# MB_adc_clk.net
KiCad netlist of a schematic drawn in Altium Designer
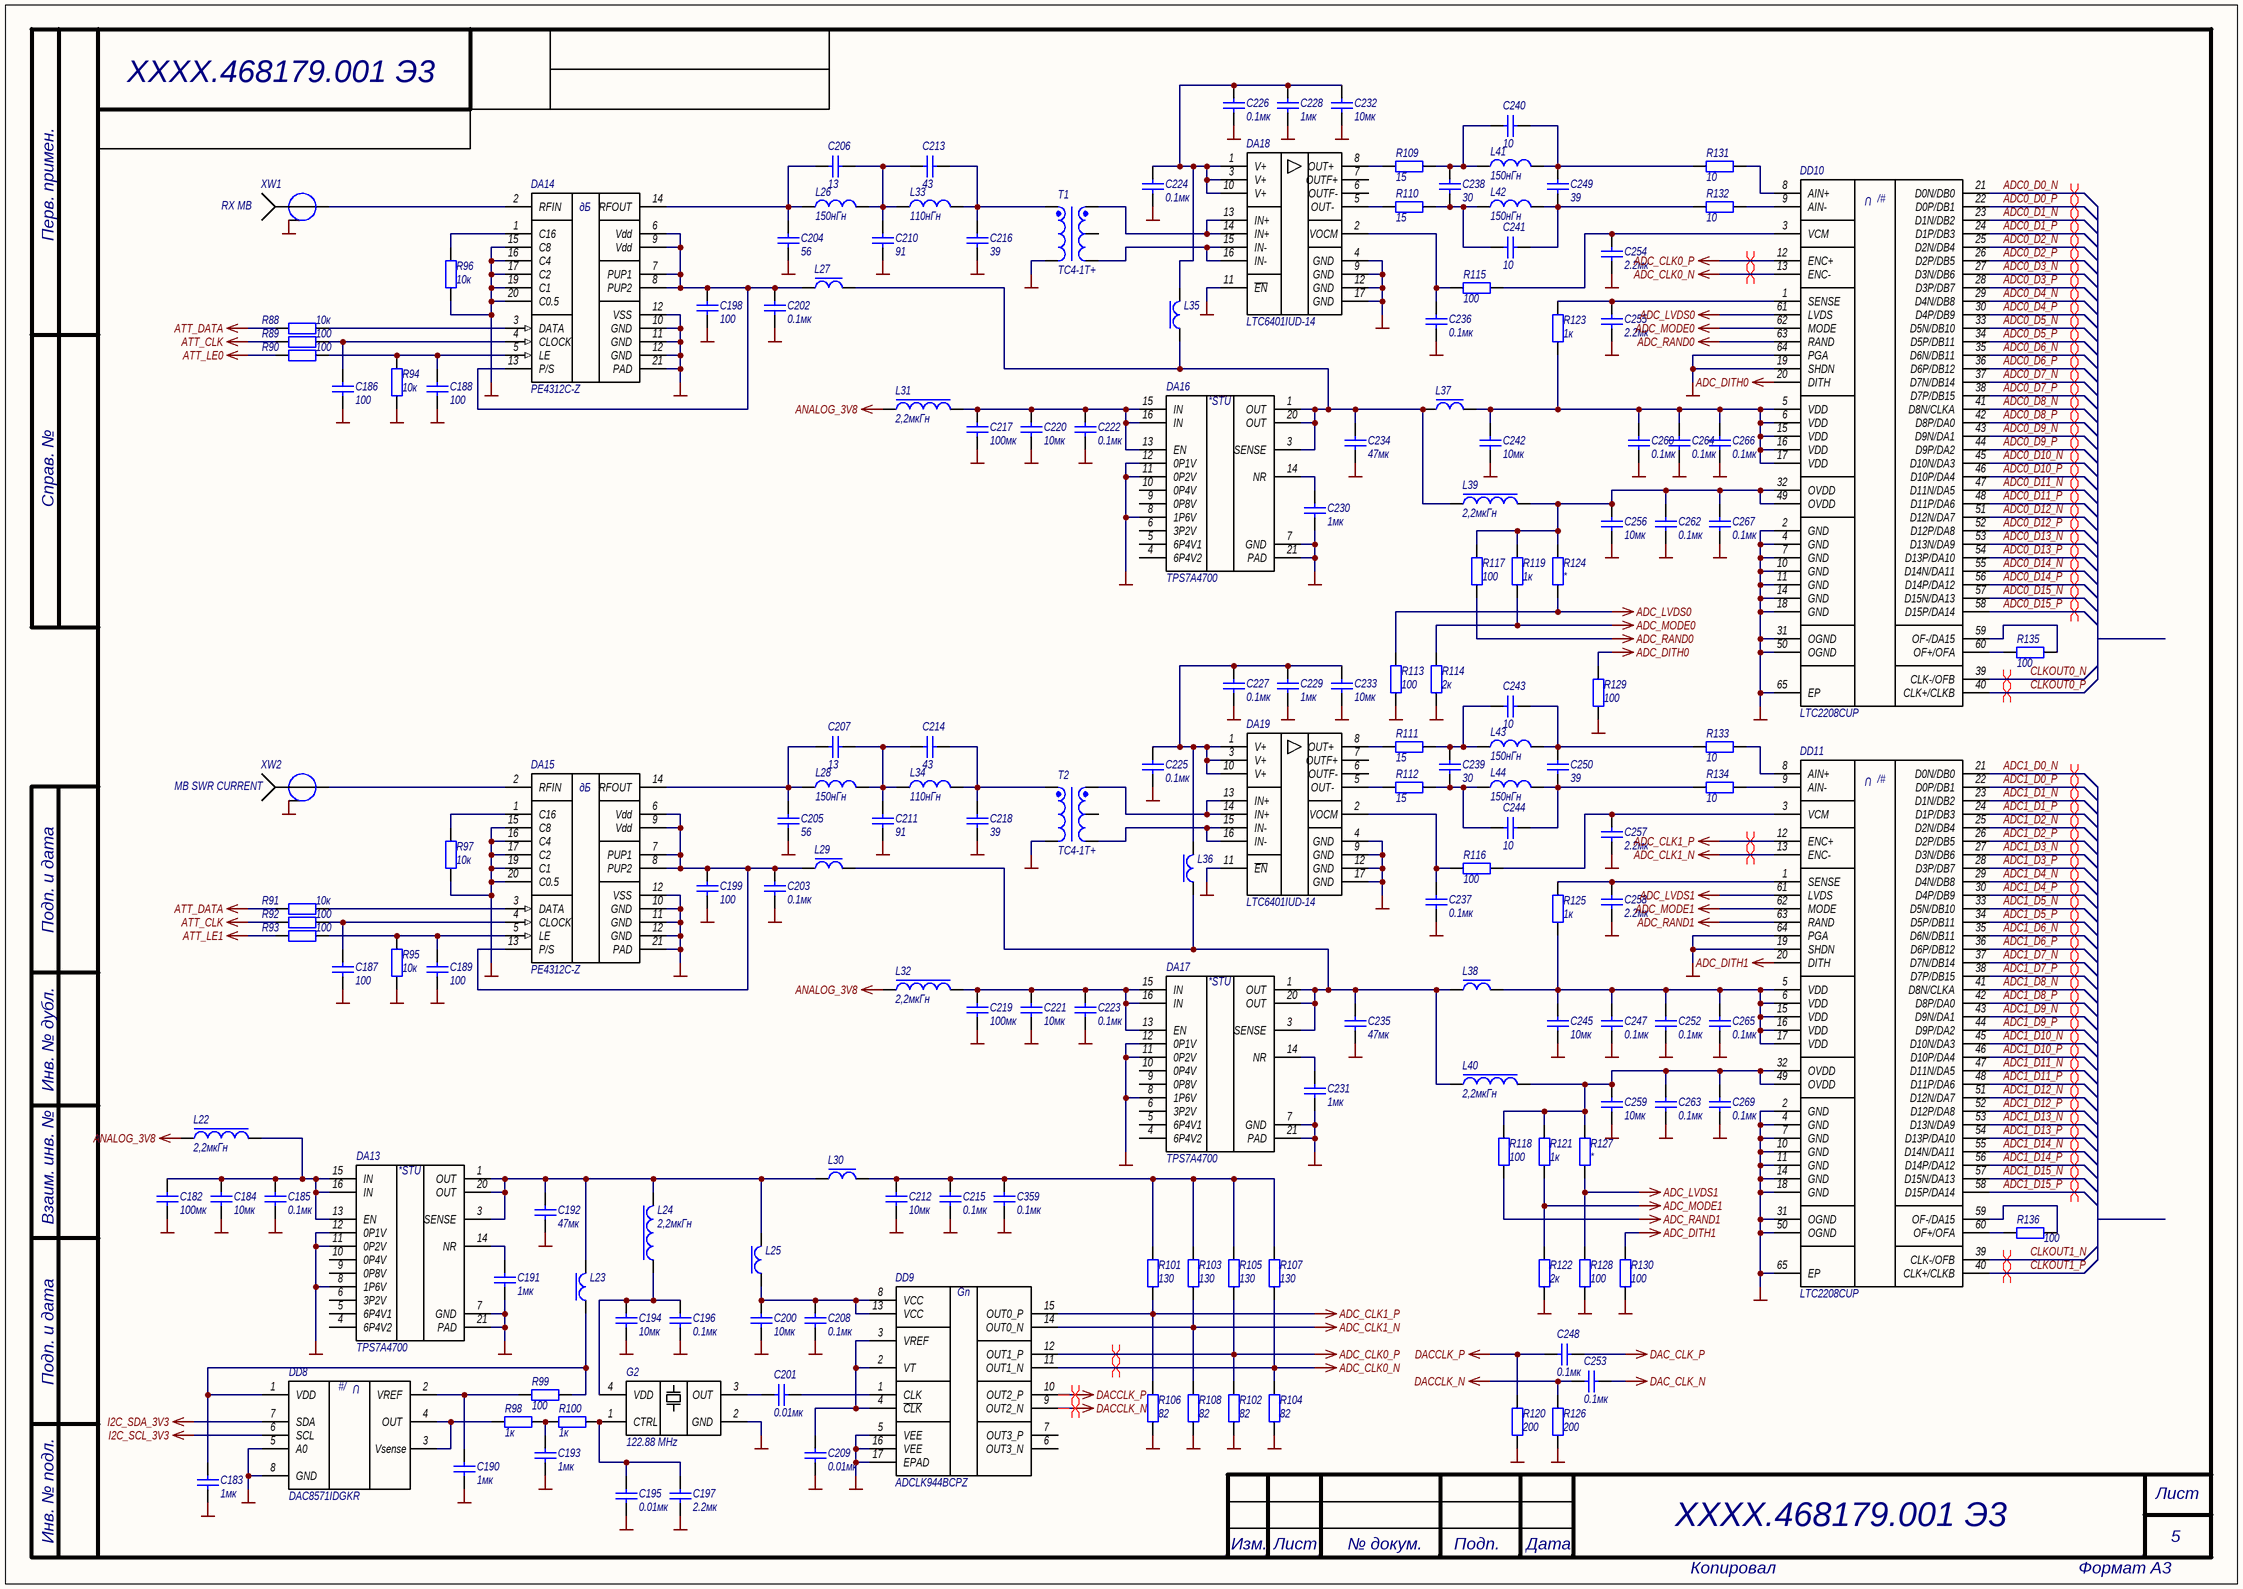
[diagram p0: MB_adc_clk.SchDoc]

(export (version "E")
  (design (tool "Eeschema 10.0.6"))
  (components
    (comp (ref "C182")
      (value "100мк")
      (footprint "CAPC3216X19L")
      (description "Кер. ЧИП-конденсатор")
      (fields (field (name "MANUFACTURER") "Murata") (field (name "TOLERANCE") "±20%"))
      (libsource (lib "nels_caps") (part "Кер.ЧИП конд. 1206 100мкФ X5R 20% 6.3В"))
    )
    (comp (ref "C183")
      (value "1мк")
      (footprint "CAPC1005X06N")
      (description "Кер. ЧИП-конденсатор")
      (fields (field (name "TOLERANCE") "±10%"))
      (libsource (lib "nels_caps") (part "Кер.ЧИП конд. 0402 1мкФ X5R 10%, 10В"))
    )
    (comp (ref "C184")
      (value "10мк")
      (footprint "CAPC1608X08L")
      (description "Кер. ЧИП-конденсатор")
      (fields (field (name "MANUFACTURER") "Murata") (field (name "TOLERANCE") "±20%"))
      (libsource (lib "nels_caps") (part "Кер.ЧИП конд. 0603 10мкФ X5R 20% 6.3В"))
    )
    (comp (ref "C185")
      (value "0.1мк")
      (footprint "CAPC1005X06N")
      (description "Кер. ЧИП-конденсатор")
      (fields (field (name "TOLERANCE") "±10%"))
      (libsource (lib "nels") (part "Кер.ЧИП конд. 0402 0.1мкФ X7R 10%, 16В"))
    )
    (comp (ref "C186")
      (value "100")
      (footprint "CAPC1005X06N")
      (description "Кер. ЧИП-конденсатор")
      (fields (field (name "TOLERANCE") "±5%"))
      (libsource (lib "nels_caps") (part "Кер.ЧИП конд. 0402 100пФ NPO 5%, 50В"))
    )
    (comp (ref "C187")
      (value "100")
      (footprint "CAPC1005X06N")
      (description "Кер. ЧИП-конденсатор")
      (fields (field (name "TOLERANCE") "±5%"))
      (libsource (lib "nels_caps") (part "Кер.ЧИП конд. 0402 100пФ NPO 5%, 50В"))
    )
    (comp (ref "C188")
      (value "100")
      (footprint "CAPC1005X06N")
      (description "Кер. ЧИП-конденсатор")
      (fields (field (name "TOLERANCE") "±5%"))
      (libsource (lib "nels_caps") (part "Кер.ЧИП конд. 0402 100пФ NPO 5%, 50В"))
    )
    (comp (ref "C189")
      (value "100")
      (footprint "CAPC1005X06N")
      (description "Кер. ЧИП-конденсатор")
      (fields (field (name "TOLERANCE") "±5%"))
      (libsource (lib "nels_caps") (part "Кер.ЧИП конд. 0402 100пФ NPO 5%, 50В"))
    )
    (comp (ref "C190")
      (value "1мк")
      (footprint "CAPC1005X06N")
      (description "Кер. ЧИП-конденсатор")
      (fields (field (name "TOLERANCE") "±10%"))
      (libsource (lib "nels_caps") (part "Кер.ЧИП конд. 0402 1мкФ X5R 10%, 10В"))
    )
    (comp (ref "C191")
      (value "1мк")
      (footprint "CAPC1005X06N")
      (description "Кер. ЧИП-конденсатор")
      (fields (field (name "TOLERANCE") "±10%"))
      (libsource (lib "nels_caps") (part "Кер.ЧИП конд. 0402 1мкФ X5R 10%, 10В"))
    )
    (comp (ref "C192")
      (value "47мк")
      (footprint "CAPC2012X12L")
      (description "Кер. ЧИП-конденсатор")
      (fields (field (name "MANUFACTURER") "Murata") (field (name "TOLERANCE") "±20%"))
      (libsource (lib "nels_caps") (part "Кер.ЧИП конд. 0805 47мкФ X5R 20% 10В"))
    )
    (comp (ref "C193")
      (value "1мк")
      (footprint "CAPC1005X06N")
      (description "Кер. ЧИП-конденсатор")
      (fields (field (name "TOLERANCE") "±10%"))
      (libsource (lib "nels_caps") (part "Кер.ЧИП конд. 0402 1мкФ X5R 10%, 10В"))
    )
    (comp (ref "C194")
      (value "10мк")
      (footprint "CAPC1608X08L")
      (description "Кер. ЧИП-конденсатор")
      (fields (field (name "MANUFACTURER") "Murata") (field (name "TOLERANCE") "±20%"))
      (libsource (lib "nels_caps") (part "Кер.ЧИП конд. 0603 10мкФ X5R 20% 6.3В"))
    )
    (comp (ref "C195")
      (value "0.01мк")
      (footprint "CAPC1005X06N")
      (description "Кер. ЧИП-конденсатор")
      (fields (field (name "TOLERANCE") "±20%"))
      (libsource (lib "nels_caps") (part "Кер.ЧИП конд. 0402 0.01мкФ X7R 10%, 50В"))
    )
    (comp (ref "C196")
      (value "0.1мк")
      (footprint "CAPC1005X06N")
      (description "Кер. ЧИП-конденсатор")
      (fields (field (name "TOLERANCE") "±10%"))
      (libsource (lib "nels") (part "Кер.ЧИП конд. 0402 0.1мкФ X7R 10%, 16В"))
    )
    (comp (ref "C197")
      (value "2.2мк")
      (footprint "CAPC1005X06N")
      (description "Кер. ЧИП-конденсатор")
      (fields (field (name "TOLERANCE") "±20%"))
      (libsource (lib "nels_caps") (part "Кер.ЧИП конд. 0402 2.2мкФ X5R 20%, 6.3В"))
    )
    (comp (ref "C198")
      (value "100")
      (footprint "CAPC1005X06N")
      (description "Кер. ЧИП-конденсатор")
      (fields (field (name "TOLERANCE") "±5%"))
      (libsource (lib "nels_caps") (part "Кер.ЧИП конд. 0402 100пФ NPO 5%, 50В"))
    )
    (comp (ref "C199")
      (value "100")
      (footprint "CAPC1005X06N")
      (description "Кер. ЧИП-конденсатор")
      (fields (field (name "TOLERANCE") "±5%"))
      (libsource (lib "nels_caps") (part "Кер.ЧИП конд. 0402 100пФ NPO 5%, 50В"))
    )
    (comp (ref "C200")
      (value "10мк")
      (footprint "CAPC1608X08L")
      (description "Кер. ЧИП-конденсатор")
      (fields (field (name "MANUFACTURER") "Murata") (field (name "TOLERANCE") "±20%"))
      (libsource (lib "nels_caps") (part "Кер.ЧИП конд. 0603 10мкФ X5R 20% 6.3В"))
    )
    (comp (ref "C201")
      (value "0.01мк")
      (footprint "CAPC1005X06N")
      (description "Кер. ЧИП-конденсатор")
      (fields (field (name "TOLERANCE") "±20%"))
      (libsource (lib "nels_caps") (part "Кер.ЧИП конд. 0402 0.01мкФ X7R 10%, 50В"))
    )
    (comp (ref "C202")
      (value "0.1мк")
      (footprint "CAPC1005X06N")
      (description "Кер. ЧИП-конденсатор")
      (fields (field (name "TOLERANCE") "±10%"))
      (libsource (lib "nels") (part "Кер.ЧИП конд. 0402 0.1мкФ X7R 10%, 16В"))
    )
    (comp (ref "C203")
      (value "0.1мк")
      (footprint "CAPC1005X06N")
      (description "Кер. ЧИП-конденсатор")
      (fields (field (name "TOLERANCE") "±10%"))
      (libsource (lib "nels") (part "Кер.ЧИП конд. 0402 0.1мкФ X7R 10%, 16В"))
    )
    (comp (ref "C204")
      (value "56")
      (footprint "CAPC1005X06N")
      (description "Кер. ЧИП-конденсатор")
      (fields (field (name "TOLERANCE") "±5%"))
      (libsource (lib "nels_caps") (part "Кер.ЧИП конд. 0402 56пФ NPO 5%, 50В"))
    )
    (comp (ref "C205")
      (value "56")
      (footprint "CAPC1005X06N")
      (description "Кер. ЧИП-конденсатор")
      (fields (field (name "TOLERANCE") "±5%"))
      (libsource (lib "nels_caps") (part "Кер.ЧИП конд. 0402 56пФ NPO 5%, 50В"))
    )
    (comp (ref "C206")
      (value "13")
      (footprint "CAPC1005X06N")
      (description "Кер. ЧИП-конденсатор")
      (fields (field (name "TOLERANCE") "±5%"))
      (libsource (lib "nels_caps") (part "Кер.ЧИП конд. 0402 13пФ NPO 5%, 50В"))
    )
    (comp (ref "C207")
      (value "13")
      (footprint "CAPC1005X06N")
      (description "Кер. ЧИП-конденсатор")
      (fields (field (name "TOLERANCE") "±5%"))
      (libsource (lib "nels_caps") (part "Кер.ЧИП конд. 0402 13пФ NPO 5%, 50В"))
    )
    (comp (ref "C208")
      (value "0.1мк")
      (footprint "CAPC1005X06N")
      (description "Кер. ЧИП-конденсатор")
      (fields (field (name "TOLERANCE") "±10%"))
      (libsource (lib "nels") (part "Кер.ЧИП конд. 0402 0.1мкФ X7R 10%, 16В"))
    )
    (comp (ref "C209")
      (value "0.01мк")
      (footprint "CAPC1005X06N")
      (description "Кер. ЧИП-конденсатор")
      (fields (field (name "TOLERANCE") "±20%"))
      (libsource (lib "nels_caps") (part "Кер.ЧИП конд. 0402 0.01мкФ X7R 10%, 50В"))
    )
    (comp (ref "C210")
      (value "91")
      (footprint "CAPC1005X06N")
      (description "Кер. ЧИП-конденсатор")
      (fields (field (name "TOLERANCE") "±5%"))
      (libsource (lib "nels_caps") (part "Кер.ЧИП конд. 0402 91пФ NPO 5%, 50В"))
    )
    (comp (ref "C211")
      (value "91")
      (footprint "CAPC1005X06N")
      (description "Кер. ЧИП-конденсатор")
      (fields (field (name "TOLERANCE") "±5%"))
      (libsource (lib "nels_caps") (part "Кер.ЧИП конд. 0402 91пФ NPO 5%, 50В"))
    )
    (comp (ref "C212")
      (value "10мк")
      (footprint "CAPC1608X08L")
      (description "Кер. ЧИП-конденсатор")
      (fields (field (name "MANUFACTURER") "Murata") (field (name "TOLERANCE") "±20%"))
      (libsource (lib "nels_caps") (part "Кер.ЧИП конд. 0603 10мкФ X5R 20% 6.3В"))
    )
    (comp (ref "C213")
      (value "43")
      (footprint "CAPC1005X06N")
      (description "Кер. ЧИП-конденсатор")
      (fields (field (name "TOLERANCE") "±5%"))
      (libsource (lib "nels_caps") (part "Кер.ЧИП конд. 0402 43пФ NPO 5%, 50В"))
    )
    (comp (ref "C214")
      (value "43")
      (footprint "CAPC1005X06N")
      (description "Кер. ЧИП-конденсатор")
      (fields (field (name "TOLERANCE") "±5%"))
      (libsource (lib "nels_caps") (part "Кер.ЧИП конд. 0402 43пФ NPO 5%, 50В"))
    )
    (comp (ref "C215")
      (value "0.1мк")
      (footprint "CAPC1005X06N")
      (description "Кер. ЧИП-конденсатор")
      (fields (field (name "TOLERANCE") "±10%"))
      (libsource (lib "nels") (part "Кер.ЧИП конд. 0402 0.1мкФ X7R 10%, 16В"))
    )
    (comp (ref "C216")
      (value "39")
      (footprint "CAPC1005X06N")
      (description "Кер. ЧИП-конденсатор")
      (fields (field (name "TOLERANCE") "±5%"))
      (libsource (lib "nels_caps") (part "Кер.ЧИП конд. 0402 39пФ NPO 5%, 50В"))
    )
    (comp (ref "C217")
      (value "100мк")
      (footprint "CAPC3216X19L")
      (description "Кер. ЧИП-конденсатор")
      (fields (field (name "MANUFACTURER") "Murata") (field (name "TOLERANCE") "±20%"))
      (libsource (lib "nels_caps") (part "Кер.ЧИП конд. 1206 100мкФ X5R 20% 6.3В"))
    )
    (comp (ref "C218")
      (value "39")
      (footprint "CAPC1005X06N")
      (description "Кер. ЧИП-конденсатор")
      (fields (field (name "TOLERANCE") "±5%"))
      (libsource (lib "nels_caps") (part "Кер.ЧИП конд. 0402 39пФ NPO 5%, 50В"))
    )
    (comp (ref "C219")
      (value "100мк")
      (footprint "CAPC3216X19L")
      (description "Кер. ЧИП-конденсатор")
      (fields (field (name "MANUFACTURER") "Murata") (field (name "TOLERANCE") "±20%"))
      (libsource (lib "nels_caps") (part "Кер.ЧИП конд. 1206 100мкФ X5R 20% 6.3В"))
    )
    (comp (ref "C220")
      (value "10мк")
      (footprint "CAPC1608X08L")
      (description "Кер. ЧИП-конденсатор")
      (fields (field (name "MANUFACTURER") "Murata") (field (name "TOLERANCE") "±20%"))
      (libsource (lib "nels_caps") (part "Кер.ЧИП конд. 0603 10мкФ X5R 20% 6.3В"))
    )
    (comp (ref "C221")
      (value "10мк")
      (footprint "CAPC1608X08L")
      (description "Кер. ЧИП-конденсатор")
      (fields (field (name "MANUFACTURER") "Murata") (field (name "TOLERANCE") "±20%"))
      (libsource (lib "nels_caps") (part "Кер.ЧИП конд. 0603 10мкФ X5R 20% 6.3В"))
    )
    (comp (ref "C222")
      (value "0.1мк")
      (footprint "CAPC1005X06N")
      (description "Кер. ЧИП-конденсатор")
      (fields (field (name "TOLERANCE") "±10%"))
      (libsource (lib "nels") (part "Кер.ЧИП конд. 0402 0.1мкФ X7R 10%, 16В"))
    )
    (comp (ref "C223")
      (value "0.1мк")
      (footprint "CAPC1005X06N")
      (description "Кер. ЧИП-конденсатор")
      (fields (field (name "TOLERANCE") "±10%"))
      (libsource (lib "nels") (part "Кер.ЧИП конд. 0402 0.1мкФ X7R 10%, 16В"))
    )
    (comp (ref "C224")
      (value "0.1мк")
      (footprint "CAPC1005X06N")
      (description "Кер. ЧИП-конденсатор")
      (fields (field (name "TOLERANCE") "±10%"))
      (libsource (lib "nels") (part "Кер.ЧИП конд. 0402 0.1мкФ X7R 10%, 16В"))
    )
    (comp (ref "C225")
      (value "0.1мк")
      (footprint "CAPC1005X06N")
      (description "Кер. ЧИП-конденсатор")
      (fields (field (name "TOLERANCE") "±10%"))
      (libsource (lib "nels") (part "Кер.ЧИП конд. 0402 0.1мкФ X7R 10%, 16В"))
    )
    (comp (ref "C226")
      (value "0.1мк")
      (footprint "CAPC1005X06N")
      (description "Кер. ЧИП-конденсатор")
      (fields (field (name "TOLERANCE") "±10%"))
      (libsource (lib "nels") (part "Кер.ЧИП конд. 0402 0.1мкФ X7R 10%, 16В"))
    )
    (comp (ref "C227")
      (value "0.1мк")
      (footprint "CAPC1005X06N")
      (description "Кер. ЧИП-конденсатор")
      (fields (field (name "TOLERANCE") "±10%"))
      (libsource (lib "nels") (part "Кер.ЧИП конд. 0402 0.1мкФ X7R 10%, 16В"))
    )
    (comp (ref "C228")
      (value "1мк")
      (footprint "CAPC1005X06N")
      (description "Кер. ЧИП-конденсатор")
      (fields (field (name "TOLERANCE") "±10%"))
      (libsource (lib "nels") (part "Кер.ЧИП конд. 0402 1мкФ X5R 10%, 10В"))
    )
    (comp (ref "C229")
      (value "1мк")
      (footprint "CAPC1005X06N")
      (description "Кер. ЧИП-конденсатор")
      (fields (field (name "TOLERANCE") "±10%"))
      (libsource (lib "nels") (part "Кер.ЧИП конд. 0402 1мкФ X5R 10%, 10В"))
    )
    (comp (ref "C230")
      (value "1мк")
      (footprint "CAPC1005X06N")
      (description "Кер. ЧИП-конденсатор")
      (fields (field (name "TOLERANCE") "±10%"))
      (libsource (lib "nels_caps") (part "Кер.ЧИП конд. 0402 1мкФ X5R 10%, 10В"))
    )
    (comp (ref "C231")
      (value "1мк")
      (footprint "CAPC1005X06N")
      (description "Кер. ЧИП-конденсатор")
      (fields (field (name "TOLERANCE") "±10%"))
      (libsource (lib "nels_caps") (part "Кер.ЧИП конд. 0402 1мкФ X5R 10%, 10В"))
    )
    (comp (ref "C232")
      (value "10мк")
      (footprint "CAPC1608X08L")
      (description "Кер. ЧИП-конденсатор")
      (fields (field (name "MANUFACTURER") "Murata") (field (name "TOLERANCE") "±20%"))
      (libsource (lib "nels_caps") (part "Кер.ЧИП конд. 0603 10мкФ X5R 20% 6.3В"))
    )
    (comp (ref "C233")
      (value "10мк")
      (footprint "CAPC1608X08L")
      (description "Кер. ЧИП-конденсатор")
      (fields (field (name "MANUFACTURER") "Murata") (field (name "TOLERANCE") "±20%"))
      (libsource (lib "nels_caps") (part "Кер.ЧИП конд. 0603 10мкФ X5R 20% 6.3В"))
    )
    (comp (ref "C234")
      (value "47мк")
      (footprint "CAPC2012X12L")
      (description "Кер. ЧИП-конденсатор")
      (fields (field (name "MANUFACTURER") "Murata") (field (name "TOLERANCE") "±20%"))
      (libsource (lib "nels_caps") (part "Кер.ЧИП конд. 0805 47мкФ X5R 20% 10В"))
    )
    (comp (ref "C235")
      (value "47мк")
      (footprint "CAPC2012X12L")
      (description "Кер. ЧИП-конденсатор")
      (fields (field (name "MANUFACTURER") "Murata") (field (name "TOLERANCE") "±20%"))
      (libsource (lib "nels_caps") (part "Кер.ЧИП конд. 0805 47мкФ X5R 20% 10В"))
    )
    (comp (ref "C236")
      (value "0.1мк")
      (footprint "CAPC1005X06N")
      (description "Кер. ЧИП-конденсатор")
      (fields (field (name "TOLERANCE") "±10%"))
      (libsource (lib "nels") (part "Кер.ЧИП конд. 0402 0.1мкФ X7R 10%, 16В"))
    )
    (comp (ref "C237")
      (value "0.1мк")
      (footprint "CAPC1005X06N")
      (description "Кер. ЧИП-конденсатор")
      (fields (field (name "TOLERANCE") "±10%"))
      (libsource (lib "nels") (part "Кер.ЧИП конд. 0402 0.1мкФ X7R 10%, 16В"))
    )
    (comp (ref "C238")
      (value "30")
      (footprint "CAPC1005X06N")
      (description "Кер. ЧИП-конденсатор")
      (fields (field (name "TOLERANCE") "±5%"))
      (libsource (lib "nels_caps") (part "Кер.ЧИП конд. 0402 30пФ NPO 5%, 50В"))
    )
    (comp (ref "C239")
      (value "30")
      (footprint "CAPC1005X06N")
      (description "Кер. ЧИП-конденсатор")
      (fields (field (name "TOLERANCE") "±5%"))
      (libsource (lib "nels_caps") (part "Кер.ЧИП конд. 0402 30пФ NPO 5%, 50В"))
    )
    (comp (ref "C240")
      (value "10")
      (footprint "CAPC1005X06N")
      (description "Кер. ЧИП-конденсатор")
      (fields (field (name "TOLERANCE") "±5%"))
      (libsource (lib "nels_caps") (part "Кер.ЧИП конд. 0402 10пФ NPO 5%, 50В"))
    )
    (comp (ref "C241")
      (value "10")
      (footprint "CAPC1005X06N")
      (description "Кер. ЧИП-конденсатор")
      (fields (field (name "TOLERANCE") "±5%"))
      (libsource (lib "nels_caps") (part "Кер.ЧИП конд. 0402 10пФ NPO 5%, 50В"))
    )
    (comp (ref "C242")
      (value "10мк")
      (footprint "CAPC1608X08L")
      (description "Кер. ЧИП-конденсатор")
      (fields (field (name "MANUFACTURER") "Murata") (field (name "TOLERANCE") "±20%"))
      (libsource (lib "nels_caps") (part "Кер.ЧИП конд. 0603 10мкФ X5R 20% 6.3В"))
    )
    (comp (ref "C243")
      (value "10")
      (footprint "CAPC1005X06N")
      (description "Кер. ЧИП-конденсатор")
      (fields (field (name "TOLERANCE") "±5%"))
      (libsource (lib "nels_caps") (part "Кер.ЧИП конд. 0402 10пФ NPO 5%, 50В"))
    )
    (comp (ref "C244")
      (value "10")
      (footprint "CAPC1005X06N")
      (description "Кер. ЧИП-конденсатор")
      (fields (field (name "TOLERANCE") "±5%"))
      (libsource (lib "nels_caps") (part "Кер.ЧИП конд. 0402 10пФ NPO 5%, 50В"))
    )
    (comp (ref "C245")
      (value "10мк")
      (footprint "CAPC1608X08L")
      (description "Кер. ЧИП-конденсатор")
      (fields (field (name "MANUFACTURER") "Murata") (field (name "TOLERANCE") "±20%"))
      (libsource (lib "nels_caps") (part "Кер.ЧИП конд. 0603 10мкФ X5R 20% 6.3В"))
    )
    (comp (ref "C247")
      (value "0.1мк")
      (footprint "CAPC1005X06N")
      (description "Кер. ЧИП-конденсатор")
      (fields (field (name "TOLERANCE") "±10%"))
      (libsource (lib "nels") (part "Кер.ЧИП конд. 0402 0.1мкФ X7R 10%, 16В"))
    )
    (comp (ref "C248")
      (value "0.1мк")
      (footprint "CAPC1005X06N")
      (description "Кер. ЧИП-конденсатор")
      (fields (field (name "TOLERANCE") "±10%"))
      (libsource (lib "nels") (part "Кер.ЧИП конд. 0402 0.1мкФ X7R 10%, 16В"))
    )
    (comp (ref "C249")
      (value "39")
      (footprint "CAPC1005X06N")
      (description "Кер. ЧИП-конденсатор")
      (fields (field (name "TOLERANCE") "±5%"))
      (libsource (lib "nels_caps") (part "Кер.ЧИП конд. 0402 39пФ NPO 5%, 50В"))
    )
    (comp (ref "C250")
      (value "39")
      (footprint "CAPC1005X06N")
      (description "Кер. ЧИП-конденсатор")
      (fields (field (name "TOLERANCE") "±5%"))
      (libsource (lib "nels_caps") (part "Кер.ЧИП конд. 0402 39пФ NPO 5%, 50В"))
    )
    (comp (ref "C252")
      (value "0.1мк")
      (footprint "CAPC1005X06N")
      (description "Кер. ЧИП-конденсатор")
      (fields (field (name "TOLERANCE") "±10%"))
      (libsource (lib "nels") (part "Кер.ЧИП конд. 0402 0.1мкФ X7R 10%, 16В"))
    )
    (comp (ref "C253")
      (value "0.1мк")
      (footprint "CAPC1005X06N")
      (description "Кер. ЧИП-конденсатор")
      (fields (field (name "TOLERANCE") "±10%"))
      (libsource (lib "nels") (part "Кер.ЧИП конд. 0402 0.1мкФ X7R 10%, 16В"))
    )
    (comp (ref "C254")
      (value "2.2мк")
      (footprint "CAPC1005X06N")
      (description "Кер. ЧИП-конденсатор")
      (fields (field (name "TOLERANCE") "±20%"))
      (libsource (lib "nels_caps") (part "Кер.ЧИП конд. 0402 2.2мкФ X5R 20%, 6.3В"))
    )
    (comp (ref "C255")
      (value "2.2мк")
      (footprint "CAPC1005X06N")
      (description "Кер. ЧИП-конденсатор")
      (fields (field (name "TOLERANCE") "±20%"))
      (libsource (lib "nels_caps") (part "Кер.ЧИП конд. 0402 2.2мкФ X5R 20%, 6.3В"))
    )
    (comp (ref "C256")
      (value "10мк")
      (footprint "CAPC1608X08L")
      (description "Кер. ЧИП-конденсатор")
      (fields (field (name "MANUFACTURER") "Murata") (field (name "TOLERANCE") "±20%"))
      (libsource (lib "nels_caps") (part "Кер.ЧИП конд. 0603 10мкФ X5R 20% 6.3В"))
    )
    (comp (ref "C257")
      (value "2.2мк")
      (footprint "CAPC1005X06N")
      (description "Кер. ЧИП-конденсатор")
      (fields (field (name "TOLERANCE") "±20%"))
      (libsource (lib "nels_caps") (part "Кер.ЧИП конд. 0402 2.2мкФ X5R 20%, 6.3В"))
    )
    (comp (ref "C258")
      (value "2.2мк")
      (footprint "CAPC1005X06N")
      (description "Кер. ЧИП-конденсатор")
      (fields (field (name "TOLERANCE") "±20%"))
      (libsource (lib "nels_caps") (part "Кер.ЧИП конд. 0402 2.2мкФ X5R 20%, 6.3В"))
    )
    (comp (ref "C259")
      (value "10мк")
      (footprint "CAPC1608X08L")
      (description "Кер. ЧИП-конденсатор")
      (fields (field (name "MANUFACTURER") "Murata") (field (name "TOLERANCE") "±20%"))
      (libsource (lib "nels_caps") (part "Кер.ЧИП конд. 0603 10мкФ X5R 20% 6.3В"))
    )
    (comp (ref "C260")
      (value "0.1мк")
      (footprint "CAPC1005X06N")
      (description "Кер. ЧИП-конденсатор")
      (fields (field (name "TOLERANCE") "±10%"))
      (libsource (lib "nels") (part "Кер.ЧИП конд. 0402 0.1мкФ X7R 10%, 16В"))
    )
    (comp (ref "C262")
      (value "0.1мк")
      (footprint "CAPC1005X06N")
      (description "Кер. ЧИП-конденсатор")
      (fields (field (name "TOLERANCE") "±10%"))
      (libsource (lib "nels") (part "Кер.ЧИП конд. 0402 0.1мкФ X7R 10%, 16В"))
    )
    (comp (ref "C263")
      (value "0.1мк")
      (footprint "CAPC1005X06N")
      (description "Кер. ЧИП-конденсатор")
      (fields (field (name "TOLERANCE") "±10%"))
      (libsource (lib "nels") (part "Кер.ЧИП конд. 0402 0.1мкФ X7R 10%, 16В"))
    )
    (comp (ref "C264")
      (value "0.1мк")
      (footprint "CAPC1005X06N")
      (description "Кер. ЧИП-конденсатор")
      (fields (field (name "TOLERANCE") "±10%"))
      (libsource (lib "nels") (part "Кер.ЧИП конд. 0402 0.1мкФ X7R 10%, 16В"))
    )
    (comp (ref "C265")
      (value "0.1мк")
      (footprint "CAPC1005X06N")
      (description "Кер. ЧИП-конденсатор")
      (fields (field (name "TOLERANCE") "±10%"))
      (libsource (lib "nels") (part "Кер.ЧИП конд. 0402 0.1мкФ X7R 10%, 16В"))
    )
    (comp (ref "C266")
      (value "0.1мк")
      (footprint "CAPC1005X06N")
      (description "Кер. ЧИП-конденсатор")
      (fields (field (name "TOLERANCE") "±10%"))
      (libsource (lib "nels") (part "Кер.ЧИП конд. 0402 0.1мкФ X7R 10%, 16В"))
    )
    (comp (ref "C267")
      (value "0.1мк")
      (footprint "CAPC1005X06N")
      (description "Кер. ЧИП-конденсатор")
      (fields (field (name "TOLERANCE") "±10%"))
      (libsource (lib "nels") (part "Кер.ЧИП конд. 0402 0.1мкФ X7R 10%, 16В"))
    )
    (comp (ref "C269")
      (value "0.1мк")
      (footprint "CAPC1005X06N")
      (description "Кер. ЧИП-конденсатор")
      (fields (field (name "TOLERANCE") "±10%"))
      (libsource (lib "nels") (part "Кер.ЧИП конд. 0402 0.1мкФ X7R 10%, 16В"))
    )
    (comp (ref "C359")
      (value "0.1мк")
      (footprint "CAPC1005X06N")
      (description "Кер. ЧИП-конденсатор")
      (fields (field (name "TOLERANCE") "±10%"))
      (libsource (lib "nels") (part "Кер.ЧИП конд. 0402 0.1мкФ X7R 10%, 16В"))
    )
    (comp (ref "DA13")
      (value "TPS7A4700")
      (footprint "QFN65P500X500X100_HS-21L")
      (description "36-V, 1-A, 4-µVRMS, RF LDO Voltage Regulator")
      (fields (field (name "MANUFACTURER") "TI"))
      (libsource (lib "nels_chip") (part "Микросхема TPS7A4700RGW"))
    )
    (comp (ref "DA14")
      (value "PE4312C-Z")
      (footprint "QFN50P400X400X80_HS-21L")
      (description "RF Digital Step Attenuator 6-bit, 31.5 dB, 1 MHz–4 GHz")
      (fields (field (name "MANUFACTURER") "Peregrine"))
      (libsource (lib "nels_chip") (part "Микросхема PE4312C-Z"))
    )
    (comp (ref "DA15")
      (value "PE4312C-Z")
      (footprint "QFN50P400X400X80_HS-21L")
      (description "RF Digital Step Attenuator 6-bit, 31.5 dB, 1 MHz–4 GHz")
      (fields (field (name "MANUFACTURER") "Peregrine"))
      (libsource (lib "nels_chip") (part "Микросхема PE4312C-Z"))
    )
    (comp (ref "DA16")
      (value "TPS7A4700")
      (footprint "QFN65P500X500X100_HS-21L")
      (description "36-V, 1-A, 4-µVRMS, RF LDO Voltage Regulator")
      (fields (field (name "MANUFACTURER") "TI"))
      (libsource (lib "nels_chip") (part "Микросхема TPS7A4700RGW"))
    )
    (comp (ref "DA17")
      (value "TPS7A4700")
      (footprint "QFN65P500X500X100_HS-21L")
      (description "36-V, 1-A, 4-µVRMS, RF LDO Voltage Regulator")
      (fields (field (name "MANUFACTURER") "TI"))
      (libsource (lib "nels_chip") (part "Микросхема TPS7A4700RGW"))
    )
    (comp (ref "DA18")
      (value "LTC6401IUD-14")
      (footprint "QFN50P300X300X75_HS-17L")
      (description "2GHz Low Noise, Low  Distortion Differential ADC  Driver for DC-140MHz")
      (fields (field (name "MANUFACTURER") "LINEAR TECHNOLOGY"))
      (libsource (lib "nels_chip") (part "Микросхема LTC6401IUD-14"))
    )
    (comp (ref "DA19")
      (value "LTC6401IUD-14")
      (footprint "QFN50P300X300X75_HS-17L")
      (description "2GHz Low Noise, Low  Distortion Differential ADC  Driver for DC-140MHz")
      (fields (field (name "MANUFACTURER") "LINEAR TECHNOLOGY"))
      (libsource (lib "nels_chip") (part "Микросхема LTC6401IUD-14"))
    )
    (comp (ref "DD8")
      (value "DAC8571IDGKR")
      (footprint "TSOP65P490X110-8L")
      (description "16-BIT, LOW POWER, VOLTAGE OUTPUT, I2C INTERFACE DIGITAL-TO-ANALOG  CONVERTER")
      (fields (field (name "MANUFACTURER") "TI"))
      (libsource (lib "nels_chip") (part "Микросхема DAC8571IDGKR"))
    )
    (comp (ref "DD9")
      (value "ADCLK944BCPZ")
      (footprint "QFN50P300X300X100_HS-17L")
      (description "2.5 V/3.3 V, Four LVPECL Outputs,  SiGe Clock Fanout Buffer")
      (fields (field (name "MANUFACTURER") "TI"))
      (libsource (lib "nels_chip") (part "Микросхема ADCLK944BCPZ"))
    )
    (comp (ref "DD10")
      (value "LTC2208CUP")
      (footprint "QFN50P900X900X100_HS-65L")
      (description "16-Bit, 130Msps ADC")
      (libsource (lib "nels_chip") (part "Микросхема LTC2208CUP"))
    )
    (comp (ref "DD11")
      (value "LTC2208CUP")
      (footprint "QFN50P900X900X100_HS-65L")
      (description "16-Bit, 130Msps ADC")
      (libsource (lib "nels_chip") (part "Микросхема LTC2208CUP"))
    )
    (comp (ref "G2")
      (value "122.88 MHz")
      (footprint "CVHD-950 Model")
      (description "122.88 MHz Ultra-Low Phase Noise Oscillator")
      (fields (field (name "MANUFACTURER") "Crystek crystals"))
      (libsource (lib "nels_other") (part "Генератор кварцевый CVHD-950-122.880"))
    )
    (comp (ref "L22")
      (value "2,2мкГн")
      (footprint "CSAB0420")
      (description "Molding Power Choke")
      (fields
        (field (name "MANUFACTURER") "Vishay")
        (field (name "MANUFACTURERPARTNUMBER") "IHLP1616ABER1R0M11")
      )
      (libsource (lib "nels_ind") (part "ЧИП индуктивность CSAB0420-2R2M"))
    )
    (comp (ref "L23")
      (value "BLM18PG121SN1D")
      (footprint "INDC1608X08L")
      (description "SMD EMI Suppression Filter EMIFIL")
      (fields (field (name "MANUFACTURER") "Murata"))
      (libsource (lib "nels_ind") (part "ЧИП дроссель 0603 BLM18PG121SN1D"))
    )
    (comp (ref "L24")
      (value "2,2мкГн")
      (footprint "CSAB0420")
      (description "Molding Power Choke")
      (fields
        (field (name "MANUFACTURER") "Vishay")
        (field (name "MANUFACTURERPARTNUMBER") "IHLP1616ABER1R0M11")
      )
      (libsource (lib "nels_ind") (part "ЧИП индуктивность CSAB0420-2R2M"))
    )
    (comp (ref "L25")
      (value "BLM18PG121SN1D")
      (footprint "INDC1608X08L")
      (description "SMD EMI Suppression Filter EMIFIL")
      (fields (field (name "MANUFACTURER") "Murata"))
      (libsource (lib "nels_ind") (part "ЧИП дроссель 0603 BLM18PG121SN1D"))
    )
    (comp (ref "L26")
      (value "150нГн")
      (footprint "INDC0805CS")
      (libsource (lib "nels_ind") (part "ЧИП индуктивность 0805CS-151XGL"))
    )
    (comp (ref "L27")
      (value "BLM18PG121SN1D")
      (footprint "INDC1608X08L")
      (description "SMD EMI Suppression Filter EMIFIL")
      (fields (field (name "MANUFACTURER") "Murata"))
      (libsource (lib "nels_ind") (part "ЧИП дроссель 0603 BLM18PG121SN1D"))
    )
    (comp (ref "L28")
      (value "150нГн")
      (footprint "INDC0805CS")
      (libsource (lib "nels_ind") (part "ЧИП индуктивность 0805CS-151XGL"))
    )
    (comp (ref "L29")
      (value "BLM18PG121SN1D")
      (footprint "INDC1608X08L")
      (description "SMD EMI Suppression Filter EMIFIL")
      (fields (field (name "MANUFACTURER") "Murata"))
      (libsource (lib "nels_ind") (part "ЧИП дроссель 0603 BLM18PG121SN1D"))
    )
    (comp (ref "L30")
      (value "BLM18PG121SN1D")
      (footprint "INDC1608X08L")
      (description "SMD EMI Suppression Filter EMIFIL")
      (fields (field (name "MANUFACTURER") "Murata"))
      (libsource (lib "nels_ind") (part "ЧИП дроссель 0603 BLM18PG121SN1D"))
    )
    (comp (ref "L31")
      (value "2,2мкГн")
      (footprint "CSAB0420")
      (description "Molding Power Choke")
      (fields
        (field (name "MANUFACTURER") "Vishay")
        (field (name "MANUFACTURERPARTNUMBER") "IHLP1616ABER1R0M11")
      )
      (libsource (lib "nels_ind") (part "ЧИП индуктивность CSAB0420-2R2M"))
    )
    (comp (ref "L32")
      (value "2,2мкГн")
      (footprint "CSAB0420")
      (description "Molding Power Choke")
      (fields
        (field (name "MANUFACTURER") "Vishay")
        (field (name "MANUFACTURERPARTNUMBER") "IHLP1616ABER1R0M11")
      )
      (libsource (lib "nels_ind") (part "ЧИП индуктивность CSAB0420-2R2M"))
    )
    (comp (ref "L33")
      (value "110нГн")
      (footprint "INDC0805CS")
      (libsource (lib "nels_ind") (part "ЧИП индуктивность 0805CS-111XGL"))
    )
    (comp (ref "L34")
      (value "110нГн")
      (footprint "INDC0805CS")
      (libsource (lib "nels_ind") (part "ЧИП индуктивность 0805CS-111XGL"))
    )
    (comp (ref "L35")
      (value "BLM18PG121SN1D")
      (footprint "INDC1608X08L")
      (description "SMD EMI Suppression Filter EMIFIL")
      (fields (field (name "MANUFACTURER") "Murata"))
      (libsource (lib "nels_ind") (part "ЧИП дроссель 0603 BLM18PG121SN1D"))
    )
    (comp (ref "L36")
      (value "BLM18PG121SN1D")
      (footprint "INDC1608X08L")
      (description "SMD EMI Suppression Filter EMIFIL")
      (fields (field (name "MANUFACTURER") "Murata"))
      (libsource (lib "nels_ind") (part "ЧИП дроссель 0603 BLM18PG121SN1D"))
    )
    (comp (ref "L37")
      (value "BLM18PG121SN1D")
      (footprint "INDC1608X08L")
      (description "SMD EMI Suppression Filter EMIFIL")
      (fields (field (name "MANUFACTURER") "Murata"))
      (libsource (lib "nels_ind") (part "ЧИП дроссель 0603 BLM18PG121SN1D"))
    )
    (comp (ref "L38")
      (value "BLM18PG121SN1D")
      (footprint "INDC1608X08L")
      (description "SMD EMI Suppression Filter EMIFIL")
      (fields (field (name "MANUFACTURER") "Murata"))
      (libsource (lib "nels_ind") (part "ЧИП дроссель 0603 BLM18PG121SN1D"))
    )
    (comp (ref "L39")
      (value "2,2мкГн")
      (footprint "CSAB0420")
      (description "Molding Power Choke")
      (fields
        (field (name "MANUFACTURER") "Vishay")
        (field (name "MANUFACTURERPARTNUMBER") "IHLP1616ABER1R0M11")
      )
      (libsource (lib "nels_ind") (part "ЧИП индуктивность CSAB0420-2R2M"))
    )
    (comp (ref "L40")
      (value "2,2мкГн")
      (footprint "CSAB0420")
      (description "Molding Power Choke")
      (fields
        (field (name "MANUFACTURER") "Vishay")
        (field (name "MANUFACTURERPARTNUMBER") "IHLP1616ABER1R0M11")
      )
      (libsource (lib "nels_ind") (part "ЧИП индуктивность CSAB0420-2R2M"))
    )
    (comp (ref "L41")
      (value "150нГн")
      (footprint "INDC0805CS")
      (libsource (lib "nels_ind") (part "ЧИП индуктивность 0805CS-150XJL"))
    )
    (comp (ref "L42")
      (value "150нГн")
      (footprint "INDC0805CS")
      (libsource (lib "nels_ind") (part "ЧИП индуктивность 0805CS-150XJL"))
    )
    (comp (ref "L43")
      (value "150нГн")
      (footprint "INDC0805CS")
      (libsource (lib "nels_ind") (part "ЧИП индуктивность 0805CS-150XJL"))
    )
    (comp (ref "L44")
      (value "150нГн")
      (footprint "INDC0805CS")
      (libsource (lib "nels_ind") (part "ЧИП индуктивность 0805CS-150XJL"))
    )
    (comp (ref "R88")
      (value "10к")
      (footprint "RESC1005X06N")
      (description "ЧИП-резистор")
      (fields (field (name "TOLERANCE") "±5%"))
      (libsource (lib "") (part "Чип резистор 0402 10 кОм, 5%_1"))
    )
    (comp (ref "R89")
      (value "100")
      (footprint "RESC1005X06N")
      (description "ЧИП-резистор")
      (fields (field (name "TOLERANCE") "±5%"))
      (libsource (lib "") (part "Чип резистор 0402 100 Ом, 5%_1"))
    )
    (comp (ref "R90")
      (value "100")
      (footprint "RESC1005X06N")
      (description "ЧИП-резистор")
      (fields (field (name "TOLERANCE") "±5%"))
      (libsource (lib "") (part "Чип резистор 0402 100 Ом, 5%_1"))
    )
    (comp (ref "R91")
      (value "10к")
      (footprint "RESC1005X06N")
      (description "ЧИП-резистор")
      (fields (field (name "TOLERANCE") "±5%"))
      (libsource (lib "") (part "Чип резистор 0402 10 кОм, 5%_1"))
    )
    (comp (ref "R92")
      (value "100")
      (footprint "RESC1005X06N")
      (description "ЧИП-резистор")
      (fields (field (name "TOLERANCE") "±5%"))
      (libsource (lib "") (part "Чип резистор 0402 100 Ом, 5%_1"))
    )
    (comp (ref "R93")
      (value "100")
      (footprint "RESC1005X06N")
      (description "ЧИП-резистор")
      (fields (field (name "TOLERANCE") "±5%"))
      (libsource (lib "") (part "Чип резистор 0402 100 Ом, 5%_1"))
    )
    (comp (ref "R94")
      (value "10к")
      (footprint "RESC1005X06N")
      (description "ЧИП-резистор")
      (fields (field (name "TOLERANCE") "±5%"))
      (libsource (lib "nels_res") (part "Чип резистор 0402 10 кОм, 5%"))
    )
    (comp (ref "R95")
      (value "10к")
      (footprint "RESC1005X06N")
      (description "ЧИП-резистор")
      (fields (field (name "TOLERANCE") "±5%"))
      (libsource (lib "nels_res") (part "Чип резистор 0402 10 кОм, 5%"))
    )
    (comp (ref "R96")
      (value "10к")
      (footprint "RESC1005X06N")
      (description "ЧИП-резистор")
      (fields (field (name "TOLERANCE") "±5%"))
      (libsource (lib "") (part "Чип резистор 0402 10 кОм, 5%_2"))
    )
    (comp (ref "R97")
      (value "10к")
      (footprint "RESC1005X06N")
      (description "ЧИП-резистор")
      (fields (field (name "TOLERANCE") "±5%"))
      (libsource (lib "") (part "Чип резистор 0402 10 кОм, 5%_2"))
    )
    (comp (ref "R98")
      (value "1к")
      (footprint "RESC1005X06N")
      (description "ЧИП-резистор")
      (fields (field (name "TOLERANCE") "±5%"))
      (libsource (lib "") (part "Чип резистор 0402 1 кОм, 5%_1"))
    )
    (comp (ref "R99")
      (value "100")
      (footprint "RESC1005X06N")
      (description "ЧИП-резистор")
      (fields (field (name "TOLERANCE") "±5%"))
      (libsource (lib "") (part "Чип резистор 0402 100 Ом, 5%_2"))
    )
    (comp (ref "R100")
      (value "1к")
      (footprint "RESC1005X06N")
      (description "ЧИП-резистор")
      (fields (field (name "TOLERANCE") "±5%"))
      (libsource (lib "") (part "Чип резистор 0402 1 кОм, 5%_1"))
    )
    (comp (ref "R101")
      (value "130")
      (footprint "RESC1005X06N")
      (description "ЧИП-резистор")
      (fields (field (name "TOLERANCE") "±5%"))
      (libsource (lib "nels_res") (part "Чип резистор 0402 130 Ом, 5%"))
    )
    (comp (ref "R102")
      (value "82")
      (footprint "RESC1005X06N")
      (description "ЧИП-резистор")
      (fields (field (name "TOLERANCE") "±5%"))
      (libsource (lib "nels_res") (part "Чип резистор 0402 82 Ом, 5%"))
    )
    (comp (ref "R103")
      (value "130")
      (footprint "RESC1005X06N")
      (description "ЧИП-резистор")
      (fields (field (name "TOLERANCE") "±5%"))
      (libsource (lib "nels_res") (part "Чип резистор 0402 130 Ом, 5%"))
    )
    (comp (ref "R104")
      (value "82")
      (footprint "RESC1005X06N")
      (description "ЧИП-резистор")
      (fields (field (name "TOLERANCE") "±5%"))
      (libsource (lib "nels_res") (part "Чип резистор 0402 82 Ом, 5%"))
    )
    (comp (ref "R105")
      (value "130")
      (footprint "RESC1005X06N")
      (description "ЧИП-резистор")
      (fields (field (name "TOLERANCE") "±5%"))
      (libsource (lib "nels_res") (part "Чип резистор 0402 130 Ом, 5%"))
    )
    (comp (ref "R106")
      (value "82")
      (footprint "RESC1005X06N")
      (description "ЧИП-резистор")
      (fields (field (name "TOLERANCE") "±5%"))
      (libsource (lib "nels_res") (part "Чип резистор 0402 82 Ом, 5%"))
    )
    (comp (ref "R107")
      (value "130")
      (footprint "RESC1005X06N")
      (description "ЧИП-резистор")
      (fields (field (name "TOLERANCE") "±5%"))
      (libsource (lib "nels_res") (part "Чип резистор 0402 130 Ом, 5%"))
    )
    (comp (ref "R108")
      (value "82")
      (footprint "RESC1005X06N")
      (description "ЧИП-резистор")
      (fields (field (name "TOLERANCE") "±5%"))
      (libsource (lib "nels_res") (part "Чип резистор 0402 82 Ом, 5%"))
    )
    (comp (ref "R109")
      (value "15")
      (footprint "RESC1005X06N")
      (description "ЧИП-резистор")
      (fields (field (name "TOLERANCE") "±5%"))
      (libsource (lib "nels_res") (part "Чип резистор 0402 15 Ом, 5%"))
    )
    (comp (ref "R110")
      (value "15")
      (footprint "RESC1005X06N")
      (description "ЧИП-резистор")
      (fields (field (name "TOLERANCE") "±5%"))
      (libsource (lib "nels_res") (part "Чип резистор 0402 15 Ом, 5%"))
    )
    (comp (ref "R111")
      (value "15")
      (footprint "RESC1005X06N")
      (description "ЧИП-резистор")
      (fields (field (name "TOLERANCE") "±5%"))
      (libsource (lib "nels_res") (part "Чип резистор 0402 15 Ом, 5%"))
    )
    (comp (ref "R112")
      (value "15")
      (footprint "RESC1005X06N")
      (description "ЧИП-резистор")
      (fields (field (name "TOLERANCE") "±5%"))
      (libsource (lib "nels_res") (part "Чип резистор 0402 15 Ом, 5%"))
    )
    (comp (ref "R113")
      (value "100")
      (footprint "RESC1005X06N")
      (description "ЧИП-резистор")
      (fields (field (name "TOLERANCE") "±5%"))
      (libsource (lib "nels_res") (part "Чип резистор 0402 100 Ом, 5%"))
    )
    (comp (ref "R114")
      (value "2к")
      (footprint "RESC1005X06N")
      (description "ЧИП-резистор")
      (fields (field (name "TOLERANCE") "±5%"))
      (libsource (lib "nels_res") (part "Чип резистор 0402 2 кОм, 5%"))
    )
    (comp (ref "R115")
      (value "100")
      (footprint "RESC1005X06N")
      (description "ЧИП-резистор")
      (fields (field (name "TOLERANCE") "±5%"))
      (libsource (lib "") (part "Чип резистор 0402 100 Ом, 5%_2"))
    )
    (comp (ref "R116")
      (value "100")
      (footprint "RESC1005X06N")
      (description "ЧИП-резистор")
      (fields (field (name "TOLERANCE") "±5%"))
      (libsource (lib "") (part "Чип резистор 0402 100 Ом, 5%_2"))
    )
    (comp (ref "R117")
      (value "100")
      (footprint "RESC1005X06N")
      (description "ЧИП-резистор")
      (fields (field (name "TOLERANCE") "±5%"))
      (libsource (lib "nels_res") (part "Чип резистор 0402 100 Ом, 5%"))
    )
    (comp (ref "R118")
      (value "100")
      (footprint "RESC1005X06N")
      (description "ЧИП-резистор")
      (fields (field (name "TOLERANCE") "±5%"))
      (libsource (lib "nels_res") (part "Чип резистор 0402 100 Ом, 5%"))
    )
    (comp (ref "R119")
      (value "1к")
      (footprint "RESC1005X06N")
      (description "ЧИП-резистор")
      (fields (field (name "TOLERANCE") "±5%"))
      (libsource (lib "nels_res") (part "Чип резистор 0402 1 кОм, 5%"))
    )
    (comp (ref "R120")
      (value "200")
      (footprint "RESC1005X06N")
      (description "ЧИП-резистор")
      (fields (field (name "TOLERANCE") "±5%"))
      (libsource (lib "nels_res") (part "Чип резистор 0402 200 Ом, 5%"))
    )
    (comp (ref "R121")
      (value "1к")
      (footprint "RESC1005X06N")
      (description "ЧИП-резистор")
      (fields (field (name "TOLERANCE") "±5%"))
      (libsource (lib "nels_res") (part "Чип резистор 0402 1 кОм, 5%"))
    )
    (comp (ref "R122")
      (value "2к")
      (footprint "RESC1005X06N")
      (description "ЧИП-резистор")
      (fields (field (name "TOLERANCE") "±5%"))
      (libsource (lib "nels_res") (part "Чип резистор 0402 2 кОм, 5%"))
    )
    (comp (ref "R123")
      (value "1к")
      (footprint "RESC1005X06N")
      (description "ЧИП-резистор")
      (fields (field (name "TOLERANCE") "±5%"))
      (libsource (lib "nels_res") (part "Чип резистор 0402 1 кОм, 5%"))
    )
    (comp (ref "R124")
      (value "*")
      (footprint "RESC1005X06N")
      (description "ЧИП-резистор")
      (fields (field (name "TOLERANCE") "±5%") (field (name "ALTIUM_VALUE") "*"))
      (libsource (lib "nels_res") (part "Чип резистор 0402 *"))
    )
    (comp (ref "R125")
      (value "1к")
      (footprint "RESC1005X06N")
      (description "ЧИП-резистор")
      (fields (field (name "TOLERANCE") "±5%"))
      (libsource (lib "nels_res") (part "Чип резистор 0402 1 кОм, 5%"))
    )
    (comp (ref "R126")
      (value "200")
      (footprint "RESC1005X06N")
      (description "ЧИП-резистор")
      (fields (field (name "TOLERANCE") "±5%"))
      (libsource (lib "nels_res") (part "Чип резистор 0402 200 Ом, 5%"))
    )
    (comp (ref "R127")
      (value "*")
      (footprint "RESC1005X06N")
      (description "ЧИП-резистор")
      (fields (field (name "TOLERANCE") "±5%") (field (name "ALTIUM_VALUE") "*"))
      (libsource (lib "nels_res") (part "Чип резистор 0402 *"))
    )
    (comp (ref "R128")
      (value "100")
      (footprint "RESC1005X06N")
      (description "ЧИП-резистор")
      (fields (field (name "TOLERANCE") "±5%"))
      (libsource (lib "nels_res") (part "Чип резистор 0402 100 Ом, 5%"))
    )
    (comp (ref "R129")
      (value "100")
      (footprint "RESC1005X06N")
      (description "ЧИП-резистор")
      (fields (field (name "TOLERANCE") "±5%"))
      (libsource (lib "nels_res") (part "Чип резистор 0402 100 Ом, 5%"))
    )
    (comp (ref "R130")
      (value "100")
      (footprint "RESC1005X06N")
      (description "ЧИП-резистор")
      (fields (field (name "TOLERANCE") "±5%"))
      (libsource (lib "nels_res") (part "Чип резистор 0402 100 Ом, 5%"))
    )
    (comp (ref "R131")
      (value "10")
      (footprint "RESC1005X06N")
      (description "ЧИП-резистор")
      (fields (field (name "TOLERANCE") "±5%"))
      (libsource (lib "nels_res") (part "Чип резистор 0402 10 Ом, 5%"))
    )
    (comp (ref "R132")
      (value "10")
      (footprint "RESC1005X06N")
      (description "ЧИП-резистор")
      (fields (field (name "TOLERANCE") "±5%"))
      (libsource (lib "nels_res") (part "Чип резистор 0402 10 Ом, 5%"))
    )
    (comp (ref "R133")
      (value "10")
      (footprint "RESC1005X06N")
      (description "ЧИП-резистор")
      (fields (field (name "TOLERANCE") "±5%"))
      (libsource (lib "nels_res") (part "Чип резистор 0402 10 Ом, 5%"))
    )
    (comp (ref "R134")
      (value "10")
      (footprint "RESC1005X06N")
      (description "ЧИП-резистор")
      (fields (field (name "TOLERANCE") "±5%"))
      (libsource (lib "nels_res") (part "Чип резистор 0402 10 Ом, 5%"))
    )
    (comp (ref "R135")
      (value "100")
      (footprint "RESC1005X06N")
      (description "ЧИП-резистор")
      (fields (field (name "TOLERANCE") "±5%"))
      (libsource (lib "") (part "Чип резистор 0402 100 Ом, 5%_1"))
    )
    (comp (ref "R136")
      (value "100")
      (footprint "RESC1005X06N")
      (description "ЧИП-резистор")
      (fields (field (name "TOLERANCE") "±5%"))
      (libsource (lib "") (part "Чип резистор 0402 100 Ом, 5%_1"))
    )
    (comp (ref "T1")
      (value "TC4-1T+")
      (footprint "SM-22 package")
      (description "RF Transformer 50Ω 0.5 to 300 MHz 1:4")
      (fields (field (name "MANUFACTURER") "minicircuits") (field (name "MANUFACTURERPARTNUMBER") "ADT2-1T+"))
      (libsource (lib "nels_ind") (part "ЧИП трансформатор TC4-1T+"))
    )
    (comp (ref "T2")
      (value "TC4-1T+")
      (footprint "SM-22 package")
      (description "RF Transformer 50Ω 0.5 to 300 MHz 1:4")
      (fields (field (name "MANUFACTURER") "minicircuits") (field (name "MANUFACTURERPARTNUMBER") "ADT2-1T+"))
      (libsource (lib "nels_ind") (part "ЧИП трансформатор TC4-1T+"))
    )
    (comp (ref "XW1")
      (value "SMA-JR")
      (footprint "SMA-JR")
      (description "SMA-JR Разъем SMA гнездо на плату, прямой угол")
      (libsource (lib "nels_conn") (part "Соединитель коаксиальный SMA-JR"))
    )
    (comp (ref "XW2")
      (value "SMA-JR")
      (footprint "SMA-JR")
      (description "SMA-JR Разъем SMA гнездо на плату, прямой угол")
      (libsource (lib "nels_conn") (part "Соединитель коаксиальный SMA-JR"))
    )
  )
  (nets
    (net (code "1") (name "/ADC0_D0_N") (class "Default")
      (node (ref "DD10") (pin "21") (pinfunction "D0N/DB0_21") (pintype "passive"))
    )
    (net (code "2") (name "/ADC0_D0_P") (class "Default")
      (node (ref "DD10") (pin "22") (pinfunction "D0P/DB1_22") (pintype "passive"))
    )
    (net (code "3") (name "/ADC0_D1_N") (class "Default")
      (node (ref "DD10") (pin "23") (pinfunction "D1N/DB2_23") (pintype "passive"))
    )
    (net (code "4") (name "/ADC0_D1_P") (class "Default")
      (node (ref "DD10") (pin "24") (pinfunction "D1P/DB3_24") (pintype "passive"))
    )
    (net (code "5") (name "/ADC0_D2_N") (class "Default")
      (node (ref "DD10") (pin "25") (pinfunction "D2N/DB4_25") (pintype "passive"))
    )
    (net (code "6") (name "/ADC0_D2_P") (class "Default")
      (node (ref "DD10") (pin "26") (pinfunction "D2P/DB5_26") (pintype "passive"))
    )
    (net (code "7") (name "/ADC0_D3_N") (class "Default")
      (node (ref "DD10") (pin "27") (pinfunction "D3N/DB6_27") (pintype "passive"))
    )
    (net (code "8") (name "/ADC0_D3_P") (class "Default")
      (node (ref "DD10") (pin "28") (pinfunction "D3P/DB7_28") (pintype "passive"))
    )
    (net (code "9") (name "/ADC0_D4_N") (class "Default")
      (node (ref "DD10") (pin "29") (pinfunction "D4N/DB8_29") (pintype "passive"))
    )
    (net (code "10") (name "/ADC0_D4_P") (class "Default")
      (node (ref "DD10") (pin "30") (pinfunction "D4P/DB9_30") (pintype "passive"))
    )
    (net (code "11") (name "/ADC0_D5_N") (class "Default")
      (node (ref "DD10") (pin "33") (pinfunction "D5N/DB10_33") (pintype "passive"))
    )
    (net (code "12") (name "/ADC0_D5_P") (class "Default")
      (node (ref "DD10") (pin "34") (pinfunction "D5P/DB11_34") (pintype "passive"))
    )
    (net (code "13") (name "/ADC0_D6_N") (class "Default")
      (node (ref "DD10") (pin "35") (pinfunction "D6N/DB11_35") (pintype "passive"))
    )
    (net (code "14") (name "/ADC0_D6_P") (class "Default")
      (node (ref "DD10") (pin "36") (pinfunction "D6P/DB12_36") (pintype "passive"))
    )
    (net (code "15") (name "/ADC0_D7_N") (class "Default")
      (node (ref "DD10") (pin "37") (pinfunction "D7N/DB14_37") (pintype "passive"))
    )
    (net (code "16") (name "/ADC0_D7_P") (class "Default")
      (node (ref "DD10") (pin "38") (pinfunction "D7P/DB15_38") (pintype "passive"))
    )
    (net (code "17") (name "/ADC0_D8_N") (class "Default")
      (node (ref "DD10") (pin "41") (pinfunction "D8N/CLKA_41") (pintype "passive"))
    )
    (net (code "18") (name "/ADC0_D8_P") (class "Default")
      (node (ref "DD10") (pin "42") (pinfunction "D8P/DA0_42") (pintype "passive"))
    )
    (net (code "19") (name "/ADC0_D9_N") (class "Default")
      (node (ref "DD10") (pin "43") (pinfunction "D9N/DA1_43") (pintype "passive"))
    )
    (net (code "20") (name "/ADC0_D9_P") (class "Default")
      (node (ref "DD10") (pin "44") (pinfunction "D9P/DA2_44") (pintype "passive"))
    )
    (net (code "21") (name "/ADC0_D10_N") (class "Default")
      (node (ref "DD10") (pin "45") (pinfunction "D10N/DA3_45") (pintype "passive"))
    )
    (net (code "22") (name "/ADC0_D10_P") (class "Default")
      (node (ref "DD10") (pin "46") (pinfunction "D10P/DA4_46") (pintype "passive"))
    )
    (net (code "23") (name "/ADC0_D11_N") (class "Default")
      (node (ref "DD10") (pin "47") (pinfunction "D11N/DA5_47") (pintype "passive"))
    )
    (net (code "24") (name "/ADC0_D11_P") (class "Default")
      (node (ref "DD10") (pin "48") (pinfunction "D11P/DA6_48") (pintype "passive"))
    )
    (net (code "25") (name "/ADC0_D12_N") (class "Default")
      (node (ref "DD10") (pin "51") (pinfunction "D12N/DA7_51") (pintype "passive"))
    )
    (net (code "26") (name "/ADC0_D12_P") (class "Default")
      (node (ref "DD10") (pin "52") (pinfunction "D12P/DA8_52") (pintype "passive"))
    )
    (net (code "27") (name "/ADC0_D13_N") (class "Default")
      (node (ref "DD10") (pin "53") (pinfunction "D13N/DA9_53") (pintype "passive"))
    )
    (net (code "28") (name "/ADC0_D13_P") (class "Default")
      (node (ref "DD10") (pin "54") (pinfunction "D13P/DA10_54") (pintype "passive"))
    )
    (net (code "29") (name "/ADC0_D14_N") (class "Default")
      (node (ref "DD10") (pin "55") (pinfunction "D14N/DA11_55") (pintype "passive"))
    )
    (net (code "30") (name "/ADC0_D14_P") (class "Default")
      (node (ref "DD10") (pin "56") (pinfunction "D14P/DA12_56") (pintype "passive"))
    )
    (net (code "31") (name "/ADC0_D15_N") (class "Default")
      (node (ref "DD10") (pin "57") (pinfunction "D15N/DA13_57") (pintype "passive"))
    )
    (net (code "32") (name "/ADC0_D15_P") (class "Default")
      (node (ref "DD10") (pin "58") (pinfunction "D15P/DA14_58") (pintype "passive"))
    )
    (net (code "33") (name "/ADC1_D0_N") (class "Default")
      (node (ref "DD11") (pin "21") (pinfunction "D0N/DB0_21") (pintype "passive"))
    )
    (net (code "34") (name "/ADC1_D0_P") (class "Default")
      (node (ref "DD11") (pin "22") (pinfunction "D0P/DB1_22") (pintype "passive"))
    )
    (net (code "35") (name "/ADC1_D1_N") (class "Default")
      (node (ref "DD11") (pin "23") (pinfunction "D1N/DB2_23") (pintype "passive"))
    )
    (net (code "36") (name "/ADC1_D1_P") (class "Default")
      (node (ref "DD11") (pin "24") (pinfunction "D1P/DB3_24") (pintype "passive"))
    )
    (net (code "37") (name "/ADC1_D2_N") (class "Default")
      (node (ref "DD11") (pin "25") (pinfunction "D2N/DB4_25") (pintype "passive"))
    )
    (net (code "38") (name "/ADC1_D2_P") (class "Default")
      (node (ref "DD11") (pin "26") (pinfunction "D2P/DB5_26") (pintype "passive"))
    )
    (net (code "39") (name "/ADC1_D3_N") (class "Default")
      (node (ref "DD11") (pin "27") (pinfunction "D3N/DB6_27") (pintype "passive"))
    )
    (net (code "40") (name "/ADC1_D3_P") (class "Default")
      (node (ref "DD11") (pin "28") (pinfunction "D3P/DB7_28") (pintype "passive"))
    )
    (net (code "41") (name "/ADC1_D4_N") (class "Default")
      (node (ref "DD11") (pin "29") (pinfunction "D4N/DB8_29") (pintype "passive"))
    )
    (net (code "42") (name "/ADC1_D4_P") (class "Default")
      (node (ref "DD11") (pin "30") (pinfunction "D4P/DB9_30") (pintype "passive"))
    )
    (net (code "43") (name "/ADC1_D5_N") (class "Default")
      (node (ref "DD11") (pin "33") (pinfunction "D5N/DB10_33") (pintype "passive"))
    )
    (net (code "44") (name "/ADC1_D5_P") (class "Default")
      (node (ref "DD11") (pin "34") (pinfunction "D5P/DB11_34") (pintype "passive"))
    )
    (net (code "45") (name "/ADC1_D6_N") (class "Default")
      (node (ref "DD11") (pin "35") (pinfunction "D6N/DB11_35") (pintype "passive"))
    )
    (net (code "46") (name "/ADC1_D6_P") (class "Default")
      (node (ref "DD11") (pin "36") (pinfunction "D6P/DB12_36") (pintype "passive"))
    )
    (net (code "47") (name "/ADC1_D7_N") (class "Default")
      (node (ref "DD11") (pin "37") (pinfunction "D7N/DB14_37") (pintype "passive"))
    )
    (net (code "48") (name "/ADC1_D7_P") (class "Default")
      (node (ref "DD11") (pin "38") (pinfunction "D7P/DB15_38") (pintype "passive"))
    )
    (net (code "49") (name "/ADC1_D8_N") (class "Default")
      (node (ref "DD11") (pin "41") (pinfunction "D8N/CLKA_41") (pintype "passive"))
    )
    (net (code "50") (name "/ADC1_D8_P") (class "Default")
      (node (ref "DD11") (pin "42") (pinfunction "D8P/DA0_42") (pintype "passive"))
    )
    (net (code "51") (name "/ADC1_D9_N") (class "Default")
      (node (ref "DD11") (pin "43") (pinfunction "D9N/DA1_43") (pintype "passive"))
    )
    (net (code "52") (name "/ADC1_D9_P") (class "Default")
      (node (ref "DD11") (pin "44") (pinfunction "D9P/DA2_44") (pintype "passive"))
    )
    (net (code "53") (name "/ADC1_D10_N") (class "Default")
      (node (ref "DD11") (pin "45") (pinfunction "D10N/DA3_45") (pintype "passive"))
    )
    (net (code "54") (name "/ADC1_D10_P") (class "Default")
      (node (ref "DD11") (pin "46") (pinfunction "D10P/DA4_46") (pintype "passive"))
    )
    (net (code "55") (name "/ADC1_D11_N") (class "Default")
      (node (ref "DD11") (pin "47") (pinfunction "D11N/DA5_47") (pintype "passive"))
    )
    (net (code "56") (name "/ADC1_D11_P") (class "Default")
      (node (ref "DD11") (pin "48") (pinfunction "D11P/DA6_48") (pintype "passive"))
    )
    (net (code "57") (name "/ADC1_D12_N") (class "Default")
      (node (ref "DD11") (pin "51") (pinfunction "D12N/DA7_51") (pintype "passive"))
    )
    (net (code "58") (name "/ADC1_D12_P") (class "Default")
      (node (ref "DD11") (pin "52") (pinfunction "D12P/DA8_52") (pintype "passive"))
    )
    (net (code "59") (name "/ADC1_D13_N") (class "Default")
      (node (ref "DD11") (pin "53") (pinfunction "D13N/DA9_53") (pintype "passive"))
    )
    (net (code "60") (name "/ADC1_D13_P") (class "Default")
      (node (ref "DD11") (pin "54") (pinfunction "D13P/DA10_54") (pintype "passive"))
    )
    (net (code "61") (name "/ADC1_D14_N") (class "Default")
      (node (ref "DD11") (pin "55") (pinfunction "D14N/DA11_55") (pintype "passive"))
    )
    (net (code "62") (name "/ADC1_D14_P") (class "Default")
      (node (ref "DD11") (pin "56") (pinfunction "D14P/DA12_56") (pintype "passive"))
    )
    (net (code "63") (name "/ADC1_D15_N") (class "Default")
      (node (ref "DD11") (pin "57") (pinfunction "D15N/DA13_57") (pintype "passive"))
    )
    (net (code "64") (name "/ADC1_D15_P") (class "Default")
      (node (ref "DD11") (pin "58") (pinfunction "D15P/DA14_58") (pintype "passive"))
    )
    (net (code "65") (name "/CLKOUT0_N") (class "Default")
      (node (ref "DD10") (pin "39") (pinfunction "CLK-/OFB_39") (pintype "passive"))
    )
    (net (code "66") (name "/CLKOUT0_P") (class "Default")
      (node (ref "DD10") (pin "40") (pinfunction "CLK+/CLKB_40") (pintype "passive"))
    )
    (net (code "67") (name "/CLKOUT1_N") (class "Default")
      (node (ref "DD11") (pin "39") (pinfunction "CLK-/OFB_39") (pintype "passive"))
    )
    (net (code "68") (name "/CLKOUT1_P") (class "Default")
      (node (ref "DD11") (pin "40") (pinfunction "CLK+/CLKB_40") (pintype "passive"))
    )
    (net (code "69") (name "ADC_CLK0_N") (class "Default")
      (node (ref "DD10") (pin "13") (pinfunction "ENC-_13") (pintype "passive"))
      (node (ref "DD9") (pin "11") (pinfunction "OUT1_N_11") (pintype "passive"))
      (node (ref "R104") (pin "1") (pinfunction "1_1") (pintype "passive"))
      (node (ref "R107") (pin "2") (pinfunction "2_2") (pintype "passive"))
    )
    (net (code "70") (name "ADC_CLK0_P") (class "Default")
      (node (ref "DD10") (pin "12") (pinfunction "ENC+_12") (pintype "passive"))
      (node (ref "DD9") (pin "12") (pinfunction "OUT1_P_12") (pintype "passive"))
      (node (ref "R102") (pin "1") (pinfunction "1_1") (pintype "passive"))
      (node (ref "R105") (pin "2") (pinfunction "2_2") (pintype "passive"))
    )
    (net (code "71") (name "ADC_CLK1_N") (class "Default")
      (node (ref "DD11") (pin "13") (pinfunction "ENC-_13") (pintype "passive"))
      (node (ref "DD9") (pin "14") (pinfunction "OUT0_N_14") (pintype "passive"))
      (node (ref "R103") (pin "2") (pinfunction "2_2") (pintype "passive"))
      (node (ref "R108") (pin "1") (pinfunction "1_1") (pintype "passive"))
    )
    (net (code "72") (name "ADC_CLK1_P") (class "Default")
      (node (ref "DD11") (pin "12") (pinfunction "ENC+_12") (pintype "passive"))
      (node (ref "DD9") (pin "15") (pinfunction "OUT0_P_15") (pintype "passive"))
      (node (ref "R101") (pin "2") (pinfunction "2_2") (pintype "passive"))
      (node (ref "R106") (pin "1") (pinfunction "1_1") (pintype "passive"))
    )
    (net (code "73") (name "ADC_DITH0") (class "Default")
      (node (ref "DD10") (pin "20") (pinfunction "DITH_20") (pintype "passive"))
      (node (ref "R129") (pin "1") (pinfunction "1_1") (pintype "passive"))
    )
    (net (code "74") (name "ADC_DITH1") (class "Default")
      (node (ref "DD11") (pin "20") (pinfunction "DITH_20") (pintype "passive"))
      (node (ref "R130") (pin "1") (pinfunction "1_1") (pintype "passive"))
    )
    (net (code "75") (name "ADC_LVDS0") (class "Default")
      (node (ref "DD10") (pin "61") (pinfunction "LVDS_61") (pintype "passive"))
      (node (ref "R113") (pin "1") (pinfunction "1_1") (pintype "passive"))
      (node (ref "R124") (pin "2") (pinfunction "2_2") (pintype "passive"))
    )
    (net (code "76") (name "ADC_LVDS1") (class "Default")
      (node (ref "DD11") (pin "61") (pinfunction "LVDS_61") (pintype "passive"))
      (node (ref "R127") (pin "2") (pinfunction "2_2") (pintype "passive"))
      (node (ref "R128") (pin "1") (pinfunction "1_1") (pintype "passive"))
    )
    (net (code "77") (name "ADC_MODE0") (class "Default")
      (node (ref "DD10") (pin "62") (pinfunction "MODE_62") (pintype "passive"))
      (node (ref "R114") (pin "1") (pinfunction "1_1") (pintype "passive"))
      (node (ref "R119") (pin "2") (pinfunction "2_2") (pintype "passive"))
    )
    (net (code "78") (name "ADC_MODE1") (class "Default")
      (node (ref "DD11") (pin "62") (pinfunction "MODE_62") (pintype "passive"))
      (node (ref "R121") (pin "2") (pinfunction "2_2") (pintype "passive"))
      (node (ref "R122") (pin "1") (pinfunction "1_1") (pintype "passive"))
    )
    (net (code "79") (name "ADC_RAND0") (class "Default")
      (node (ref "DD10") (pin "63") (pinfunction "RAND_63") (pintype "passive"))
      (node (ref "R117") (pin "2") (pinfunction "2_2") (pintype "passive"))
    )
    (net (code "80") (name "ADC_RAND1") (class "Default")
      (node (ref "DD11") (pin "63") (pinfunction "RAND_63") (pintype "passive"))
      (node (ref "R118") (pin "2") (pinfunction "2_2") (pintype "passive"))
    )
    (net (code "81") (name "ANALOG_3V8") (class "Default")
      (node (ref "L22") (pin "1") (pinfunction "1_1") (pintype "passive"))
      (node (ref "L31") (pin "1") (pinfunction "1_1") (pintype "passive"))
      (node (ref "L32") (pin "1") (pinfunction "1_1") (pintype "passive"))
    )
    (net (code "82") (name "ATT_CLK") (class "Default")
      (node (ref "R89") (pin "2") (pinfunction "2_2") (pintype "passive"))
      (node (ref "R92") (pin "2") (pinfunction "2_2") (pintype "passive"))
    )
    (net (code "83") (name "ATT_DATA") (class "Default")
      (node (ref "R88") (pin "2") (pinfunction "2_2") (pintype "passive"))
      (node (ref "R91") (pin "2") (pinfunction "2_2") (pintype "passive"))
    )
    (net (code "84") (name "ATT_LE0") (class "Default")
      (node (ref "R90") (pin "2") (pinfunction "2_2") (pintype "passive"))
    )
    (net (code "85") (name "ATT_LE1") (class "Default")
      (node (ref "R93") (pin "2") (pinfunction "2_2") (pintype "passive"))
    )
    (net (code "86") (name "DACCLK_N") (class "Default")
      (node (ref "C253") (pin "2") (pinfunction "2_2") (pintype "passive"))
      (node (ref "DD9") (pin "9") (pinfunction "OUT2_N_9") (pintype "passive"))
      (node (ref "R126") (pin "1") (pinfunction "1_1") (pintype "passive"))
    )
    (net (code "87") (name "DACCLK_P") (class "Default")
      (node (ref "C248") (pin "2") (pinfunction "2_2") (pintype "passive"))
      (node (ref "DD9") (pin "10") (pinfunction "OUT2_P_10") (pintype "passive"))
      (node (ref "R120") (pin "1") (pinfunction "1_1") (pintype "passive"))
    )
    (net (code "88") (name "DAC_CLK_N") (class "Default")
      (node (ref "C253") (pin "1") (pinfunction "1_1") (pintype "passive"))
    )
    (net (code "89") (name "DAC_CLK_P") (class "Default")
      (node (ref "C248") (pin "1") (pinfunction "1_1") (pintype "passive"))
    )
    (net (code "90") (name "GND") (class "Default")
      (node (ref "C182") (pin "1") (pinfunction "1_1") (pintype "passive"))
      (node (ref "C183") (pin "2") (pinfunction "2_2") (pintype "passive"))
      (node (ref "C184") (pin "1") (pinfunction "1_1") (pintype "passive"))
      (node (ref "C185") (pin "1") (pinfunction "1_1") (pintype "passive"))
      (node (ref "C186") (pin "1") (pinfunction "1_1") (pintype "passive"))
      (node (ref "C187") (pin "1") (pinfunction "1_1") (pintype "passive"))
      (node (ref "C188") (pin "1") (pinfunction "1_1") (pintype "passive"))
      (node (ref "C189") (pin "1") (pinfunction "1_1") (pintype "passive"))
      (node (ref "C190") (pin "2") (pinfunction "2_2") (pintype "passive"))
      (node (ref "C191") (pin "1") (pinfunction "1_1") (pintype "passive"))
      (node (ref "C192") (pin "1") (pinfunction "1_1") (pintype "passive"))
      (node (ref "C193") (pin "2") (pinfunction "2_2") (pintype "passive"))
      (node (ref "C194") (pin "1") (pinfunction "1_1") (pintype "passive"))
      (node (ref "C195") (pin "2") (pinfunction "2_2") (pintype "passive"))
      (node (ref "C196") (pin "1") (pinfunction "1_1") (pintype "passive"))
      (node (ref "C197") (pin "1") (pinfunction "1_1") (pintype "passive"))
      (node (ref "C198") (pin "1") (pinfunction "1_1") (pintype "passive"))
      (node (ref "C199") (pin "1") (pinfunction "1_1") (pintype "passive"))
      (node (ref "C200") (pin "1") (pinfunction "1_1") (pintype "passive"))
      (node (ref "C202") (pin "1") (pinfunction "1_1") (pintype "passive"))
      (node (ref "C203") (pin "1") (pinfunction "1_1") (pintype "passive"))
      (node (ref "C204") (pin "1") (pinfunction "1_1") (pintype "passive"))
      (node (ref "C205") (pin "1") (pinfunction "1_1") (pintype "passive"))
      (node (ref "C208") (pin "1") (pinfunction "1_1") (pintype "passive"))
      (node (ref "C209") (pin "2") (pinfunction "2_2") (pintype "passive"))
      (node (ref "C210") (pin "1") (pinfunction "1_1") (pintype "passive"))
      (node (ref "C211") (pin "1") (pinfunction "1_1") (pintype "passive"))
      (node (ref "C212") (pin "1") (pinfunction "1_1") (pintype "passive"))
      (node (ref "C215") (pin "1") (pinfunction "1_1") (pintype "passive"))
      (node (ref "C216") (pin "1") (pinfunction "1_1") (pintype "passive"))
      (node (ref "C217") (pin "1") (pinfunction "1_1") (pintype "passive"))
      (node (ref "C218") (pin "1") (pinfunction "1_1") (pintype "passive"))
      (node (ref "C219") (pin "1") (pinfunction "1_1") (pintype "passive"))
      (node (ref "C220") (pin "1") (pinfunction "1_1") (pintype "passive"))
      (node (ref "C221") (pin "1") (pinfunction "1_1") (pintype "passive"))
      (node (ref "C222") (pin "1") (pinfunction "1_1") (pintype "passive"))
      (node (ref "C223") (pin "1") (pinfunction "1_1") (pintype "passive"))
      (node (ref "C224") (pin "1") (pinfunction "1_1") (pintype "passive"))
      (node (ref "C225") (pin "1") (pinfunction "1_1") (pintype "passive"))
      (node (ref "C226") (pin "1") (pinfunction "1_1") (pintype "passive"))
      (node (ref "C227") (pin "1") (pinfunction "1_1") (pintype "passive"))
      (node (ref "C228") (pin "1") (pinfunction "1_1") (pintype "passive"))
      (node (ref "C229") (pin "1") (pinfunction "1_1") (pintype "passive"))
      (node (ref "C230") (pin "1") (pinfunction "1_1") (pintype "passive"))
      (node (ref "C231") (pin "1") (pinfunction "1_1") (pintype "passive"))
      (node (ref "C232") (pin "1") (pinfunction "1_1") (pintype "passive"))
      (node (ref "C233") (pin "1") (pinfunction "1_1") (pintype "passive"))
      (node (ref "C234") (pin "1") (pinfunction "1_1") (pintype "passive"))
      (node (ref "C235") (pin "1") (pinfunction "1_1") (pintype "passive"))
      (node (ref "C236") (pin "1") (pinfunction "1_1") (pintype "passive"))
      (node (ref "C237") (pin "1") (pinfunction "1_1") (pintype "passive"))
      (node (ref "C242") (pin "1") (pinfunction "1_1") (pintype "passive"))
      (node (ref "C245") (pin "1") (pinfunction "1_1") (pintype "passive"))
      (node (ref "C247") (pin "1") (pinfunction "1_1") (pintype "passive"))
      (node (ref "C252") (pin "1") (pinfunction "1_1") (pintype "passive"))
      (node (ref "C254") (pin "1") (pinfunction "1_1") (pintype "passive"))
      (node (ref "C255") (pin "1") (pinfunction "1_1") (pintype "passive"))
      (node (ref "C256") (pin "1") (pinfunction "1_1") (pintype "passive"))
      (node (ref "C257") (pin "1") (pinfunction "1_1") (pintype "passive"))
      (node (ref "C258") (pin "1") (pinfunction "1_1") (pintype "passive"))
      (node (ref "C259") (pin "1") (pinfunction "1_1") (pintype "passive"))
      (node (ref "C260") (pin "1") (pinfunction "1_1") (pintype "passive"))
      (node (ref "C262") (pin "1") (pinfunction "1_1") (pintype "passive"))
      (node (ref "C263") (pin "1") (pinfunction "1_1") (pintype "passive"))
      (node (ref "C264") (pin "1") (pinfunction "1_1") (pintype "passive"))
      (node (ref "C265") (pin "1") (pinfunction "1_1") (pintype "passive"))
      (node (ref "C266") (pin "1") (pinfunction "1_1") (pintype "passive"))
      (node (ref "C267") (pin "1") (pinfunction "1_1") (pintype "passive"))
      (node (ref "C269") (pin "1") (pinfunction "1_1") (pintype "passive"))
      (node (ref "C359") (pin "1") (pinfunction "1_1") (pintype "passive"))
      (node (ref "DA13") (pin "11") (pinfunction "0P2V_11") (pintype "passive"))
      (node (ref "DA13") (pin "12") (pinfunction "0P1V_12") (pintype "passive"))
      (node (ref "DA13") (pin "21") (pinfunction "PAD_21") (pintype "passive"))
      (node (ref "DA13") (pin "7") (pinfunction "GND_7") (pintype "passive"))
      (node (ref "DA13") (pin "8") (pinfunction "1P6V_8") (pintype "passive"))
      (node (ref "DA14") (pin "10") (pinfunction "GND_10") (pintype "power_in"))
      (node (ref "DA14") (pin "11") (pinfunction "GND_11") (pintype "power_in"))
      (node (ref "DA14") (pin "12") (pinfunction "VSS_12") (pintype "power_in"))
      (node (ref "DA14") (pin "15") (pinfunction "C8_15") (pintype "passive"))
      (node (ref "DA14") (pin "16") (pinfunction "C4_16") (pintype "passive"))
      (node (ref "DA14") (pin "17") (pinfunction "C2_17") (pintype "passive"))
      (node (ref "DA14") (pin "19") (pinfunction "C1_19") (pintype "passive"))
      (node (ref "DA14") (pin "20") (pinfunction "C0.5_20") (pintype "passive"))
      (node (ref "DA14") (pin "21") (pinfunction "PAD_21") (pintype "power_in"))
      (node (ref "DA15") (pin "10") (pinfunction "GND_10") (pintype "power_in"))
      (node (ref "DA15") (pin "11") (pinfunction "GND_11") (pintype "power_in"))
      (node (ref "DA15") (pin "12") (pinfunction "GND_12") (pintype "power_in"))
      (node (ref "DA15") (pin "15") (pinfunction "C8_15") (pintype "passive"))
      (node (ref "DA15") (pin "16") (pinfunction "C4_16") (pintype "passive"))
      (node (ref "DA15") (pin "17") (pinfunction "C2_17") (pintype "passive"))
      (node (ref "DA15") (pin "19") (pinfunction "C1_19") (pintype "passive"))
      (node (ref "DA15") (pin "20") (pinfunction "C0.5_20") (pintype "passive"))
      (node (ref "DA15") (pin "21") (pinfunction "PAD_21") (pintype "power_in"))
      (node (ref "DA16") (pin "11") (pinfunction "0P2V_11") (pintype "passive"))
      (node (ref "DA16") (pin "12") (pinfunction "0P1V_12") (pintype "passive"))
      (node (ref "DA16") (pin "21") (pinfunction "PAD_21") (pintype "passive"))
      (node (ref "DA16") (pin "7") (pinfunction "GND_7") (pintype "passive"))
      (node (ref "DA16") (pin "8") (pinfunction "1P6V_8") (pintype "passive"))
      (node (ref "DA17") (pin "11") (pinfunction "0P2V_11") (pintype "passive"))
      (node (ref "DA17") (pin "12") (pinfunction "0P1V_12") (pintype "passive"))
      (node (ref "DA17") (pin "21") (pinfunction "PAD_21") (pintype "passive"))
      (node (ref "DA17") (pin "7") (pinfunction "GND_7") (pintype "passive"))
      (node (ref "DA17") (pin "8") (pinfunction "1P6V_8") (pintype "passive"))
      (node (ref "DA18") (pin "11") (pinfunction "~{EN}_11") (pintype "passive"))
      (node (ref "DA18") (pin "12") (pinfunction "GND_12") (pintype "passive"))
      (node (ref "DA18") (pin "17") (pinfunction "GND_17") (pintype "passive"))
      (node (ref "DA18") (pin "4") (pinfunction "GND_4") (pintype "passive"))
      (node (ref "DA18") (pin "9") (pinfunction "GND_9") (pintype "passive"))
      (node (ref "DA19") (pin "11") (pinfunction "~{EN}_11") (pintype "passive"))
      (node (ref "DA19") (pin "12") (pinfunction "GND_12") (pintype "passive"))
      (node (ref "DA19") (pin "17") (pinfunction "GND_17") (pintype "passive"))
      (node (ref "DA19") (pin "4") (pinfunction "GND_4") (pintype "passive"))
      (node (ref "DA19") (pin "9") (pinfunction "GND_9") (pintype "passive"))
      (node (ref "DD10") (pin "10") (pinfunction "GND_10") (pintype "passive"))
      (node (ref "DD10") (pin "11") (pinfunction "GND_11") (pintype "passive"))
      (node (ref "DD10") (pin "14") (pinfunction "GND_14") (pintype "passive"))
      (node (ref "DD10") (pin "18") (pinfunction "GND_18") (pintype "passive"))
      (node (ref "DD10") (pin "19") (pinfunction "SHDN_19") (pintype "passive"))
      (node (ref "DD10") (pin "2") (pinfunction "GND_2") (pintype "passive"))
      (node (ref "DD10") (pin "31") (pinfunction "OGND_31") (pintype "passive"))
      (node (ref "DD10") (pin "4") (pinfunction "GND_4") (pintype "passive"))
      (node (ref "DD10") (pin "50") (pinfunction "OGND_50") (pintype "passive"))
      (node (ref "DD10") (pin "64") (pinfunction "PGA_64") (pintype "passive"))
      (node (ref "DD10") (pin "65") (pinfunction "EP_65") (pintype "passive"))
      (node (ref "DD10") (pin "7") (pinfunction "GND_7") (pintype "passive"))
      (node (ref "DD11") (pin "10") (pinfunction "GND_10") (pintype "passive"))
      (node (ref "DD11") (pin "11") (pinfunction "GND_11") (pintype "passive"))
      (node (ref "DD11") (pin "14") (pinfunction "GND_14") (pintype "passive"))
      (node (ref "DD11") (pin "18") (pinfunction "GND_18") (pintype "passive"))
      (node (ref "DD11") (pin "19") (pinfunction "SHDN_19") (pintype "passive"))
      (node (ref "DD11") (pin "2") (pinfunction "GND_2") (pintype "passive"))
      (node (ref "DD11") (pin "31") (pinfunction "OGND_31") (pintype "passive"))
      (node (ref "DD11") (pin "4") (pinfunction "GND_4") (pintype "passive"))
      (node (ref "DD11") (pin "50") (pinfunction "OGND_50") (pintype "passive"))
      (node (ref "DD11") (pin "64") (pinfunction "PGA_64") (pintype "passive"))
      (node (ref "DD11") (pin "65") (pinfunction "EP_65") (pintype "passive"))
      (node (ref "DD11") (pin "7") (pinfunction "GND_7") (pintype "passive"))
      (node (ref "DD8") (pin "5") (pinfunction "A0_5") (pintype "passive"))
      (node (ref "DD8") (pin "8") (pinfunction "GND_8") (pintype "passive"))
      (node (ref "DD9") (pin "16") (pinfunction "VEE_16") (pintype "passive"))
      (node (ref "DD9") (pin "17") (pinfunction "EPAD_17") (pintype "passive"))
      (node (ref "DD9") (pin "5") (pinfunction "VEE_5") (pintype "passive"))
      (node (ref "G2") (pin "2") (pinfunction "GND_2") (pintype "passive"))
      (node (ref "R102") (pin "2") (pinfunction "2_2") (pintype "passive"))
      (node (ref "R104") (pin "2") (pinfunction "2_2") (pintype "passive"))
      (node (ref "R106") (pin "2") (pinfunction "2_2") (pintype "passive"))
      (node (ref "R108") (pin "2") (pinfunction "2_2") (pintype "passive"))
      (node (ref "R113") (pin "2") (pinfunction "2_2") (pintype "passive"))
      (node (ref "R114") (pin "2") (pinfunction "2_2") (pintype "passive"))
      (node (ref "R120") (pin "2") (pinfunction "2_2") (pintype "passive"))
      (node (ref "R122") (pin "2") (pinfunction "2_2") (pintype "passive"))
      (node (ref "R126") (pin "2") (pinfunction "2_2") (pintype "passive"))
      (node (ref "R128") (pin "2") (pinfunction "2_2") (pintype "passive"))
      (node (ref "R129") (pin "2") (pinfunction "2_2") (pintype "passive"))
      (node (ref "R130") (pin "2") (pinfunction "2_2") (pintype "passive"))
      (node (ref "R94") (pin "2") (pinfunction "2_2") (pintype "passive"))
      (node (ref "R95") (pin "2") (pinfunction "2_2") (pintype "passive"))
      (node (ref "R96") (pin "1") (pinfunction "1_1") (pintype "passive"))
      (node (ref "R97") (pin "1") (pinfunction "1_1") (pintype "passive"))
      (node (ref "T1") (pin "4") (pinfunction "PRIMARY_4") (pintype "passive"))
      (node (ref "T2") (pin "4") (pinfunction "PRIMARY_4") (pintype "passive"))
      (node (ref "XW1") (pin "2") (pinfunction "2_2") (pintype "passive"))
      (node (ref "XW2") (pin "2") (pinfunction "2_2") (pintype "passive"))
    )
    (net (code "91") (name "I2C_SCL_3V3") (class "Default")
      (node (ref "DD8") (pin "6") (pinfunction "SCL_6") (pintype "passive"))
    )
    (net (code "92") (name "I2C_SDA_3V3") (class "Default")
      (node (ref "DD8") (pin "7") (pinfunction "SDA_7") (pintype "passive"))
    )
    (net (code "93") (name "Net-(C193-Pad1)") (class "Default")
      (node (ref "C193") (pin "1") (pinfunction "1_1") (pintype "passive"))
      (node (ref "R100") (pin "1") (pinfunction "1_1") (pintype "passive"))
      (node (ref "R98") (pin "2") (pinfunction "2_2") (pintype "passive"))
    )
    (net (code "94") (name "Net-(C200-Pad2)") (class "Default")
      (node (ref "C200") (pin "2") (pinfunction "2_2") (pintype "passive"))
      (node (ref "C208") (pin "2") (pinfunction "2_2") (pintype "passive"))
      (node (ref "DD9") (pin "13") (pinfunction "VCC_13") (pintype "passive"))
      (node (ref "DD9") (pin "8") (pinfunction "VCC_8") (pintype "passive"))
      (node (ref "L25") (pin "1") (pinfunction "1_1") (pintype "passive"))
    )
    (net (code "95") (name "Net-(C206-Pad1)") (class "Default")
      (node (ref "C206") (pin "1") (pinfunction "1_1") (pintype "passive"))
      (node (ref "C210") (pin "2") (pinfunction "2_2") (pintype "passive"))
      (node (ref "C213") (pin "2") (pinfunction "2_2") (pintype "passive"))
      (node (ref "L26") (pin "2") (pinfunction "2_2") (pintype "passive"))
      (node (ref "L33") (pin "1") (pinfunction "1_1") (pintype "passive"))
    )
    (net (code "96") (name "Net-(C207-Pad1)") (class "Default")
      (node (ref "C207") (pin "1") (pinfunction "1_1") (pintype "passive"))
      (node (ref "C211") (pin "2") (pinfunction "2_2") (pintype "passive"))
      (node (ref "C214") (pin "2") (pinfunction "2_2") (pintype "passive"))
      (node (ref "L28") (pin "2") (pinfunction "2_2") (pintype "passive"))
      (node (ref "L34") (pin "1") (pinfunction "1_1") (pintype "passive"))
    )
    (net (code "97") (name "Net-(C212-Pad2)") (class "Default")
      (node (ref "C212") (pin "2") (pinfunction "2_2") (pintype "passive"))
      (node (ref "C215") (pin "2") (pinfunction "2_2") (pintype "passive"))
      (node (ref "C359") (pin "2") (pinfunction "2_2") (pintype "passive"))
      (node (ref "L30") (pin "2") (pinfunction "2_2") (pintype "passive"))
      (node (ref "R101") (pin "1") (pinfunction "1_1") (pintype "passive"))
      (node (ref "R103") (pin "1") (pinfunction "1_1") (pintype "passive"))
      (node (ref "R105") (pin "1") (pinfunction "1_1") (pintype "passive"))
      (node (ref "R107") (pin "1") (pinfunction "1_1") (pintype "passive"))
    )
    (net (code "98") (name "Net-(C224-Pad2)") (class "Default")
      (node (ref "C224") (pin "2") (pinfunction "2_2") (pintype "passive"))
      (node (ref "C226") (pin "2") (pinfunction "2_2") (pintype "passive"))
      (node (ref "C228") (pin "2") (pinfunction "2_2") (pintype "passive"))
      (node (ref "C232") (pin "2") (pinfunction "2_2") (pintype "passive"))
      (node (ref "DA18") (pin "1") (pinfunction "V+_1") (pintype "passive"))
      (node (ref "DA18") (pin "10") (pinfunction "V+_10") (pintype "passive"))
      (node (ref "DA18") (pin "3") (pinfunction "V+_3") (pintype "passive"))
      (node (ref "L35") (pin "2") (pinfunction "2_2") (pintype "passive"))
    )
    (net (code "99") (name "Net-(C225-Pad2)") (class "Default")
      (node (ref "C225") (pin "2") (pinfunction "2_2") (pintype "passive"))
      (node (ref "C227") (pin "2") (pinfunction "2_2") (pintype "passive"))
      (node (ref "C229") (pin "2") (pinfunction "2_2") (pintype "passive"))
      (node (ref "C233") (pin "2") (pinfunction "2_2") (pintype "passive"))
      (node (ref "DA19") (pin "1") (pinfunction "V+_1") (pintype "passive"))
      (node (ref "DA19") (pin "10") (pinfunction "V+_10") (pintype "passive"))
      (node (ref "DA19") (pin "3") (pinfunction "V+_3") (pintype "passive"))
      (node (ref "L36") (pin "2") (pinfunction "2_2") (pintype "passive"))
    )
    (net (code "100") (name "Net-(C238-Pad1)") (class "Default")
      (node (ref "C238") (pin "1") (pinfunction "1_1") (pintype "passive"))
      (node (ref "C241") (pin "2") (pinfunction "2_2") (pintype "passive"))
      (node (ref "L42") (pin "1") (pinfunction "1_1") (pintype "passive"))
      (node (ref "R110") (pin "2") (pinfunction "2_2") (pintype "passive"))
    )
    (net (code "101") (name "Net-(C238-Pad2)") (class "Default")
      (node (ref "C238") (pin "2") (pinfunction "2_2") (pintype "passive"))
      (node (ref "C240") (pin "2") (pinfunction "2_2") (pintype "passive"))
      (node (ref "L41") (pin "1") (pinfunction "1_1") (pintype "passive"))
      (node (ref "R109") (pin "2") (pinfunction "2_2") (pintype "passive"))
    )
    (net (code "102") (name "Net-(C239-Pad1)") (class "Default")
      (node (ref "C239") (pin "1") (pinfunction "1_1") (pintype "passive"))
      (node (ref "C244") (pin "2") (pinfunction "2_2") (pintype "passive"))
      (node (ref "L44") (pin "1") (pinfunction "1_1") (pintype "passive"))
      (node (ref "R112") (pin "2") (pinfunction "2_2") (pintype "passive"))
    )
    (net (code "103") (name "Net-(C239-Pad2)") (class "Default")
      (node (ref "C239") (pin "2") (pinfunction "2_2") (pintype "passive"))
      (node (ref "C243") (pin "2") (pinfunction "2_2") (pintype "passive"))
      (node (ref "L43") (pin "1") (pinfunction "1_1") (pintype "passive"))
      (node (ref "R111") (pin "2") (pinfunction "2_2") (pintype "passive"))
    )
    (net (code "104") (name "Net-(C240-Pad1)") (class "Default")
      (node (ref "C240") (pin "1") (pinfunction "1_1") (pintype "passive"))
      (node (ref "C249") (pin "2") (pinfunction "2_2") (pintype "passive"))
      (node (ref "L41") (pin "2") (pinfunction "2_2") (pintype "passive"))
      (node (ref "R131") (pin "1") (pinfunction "1_1") (pintype "passive"))
    )
    (net (code "105") (name "Net-(C241-Pad1)") (class "Default")
      (node (ref "C241") (pin "1") (pinfunction "1_1") (pintype "passive"))
      (node (ref "C249") (pin "1") (pinfunction "1_1") (pintype "passive"))
      (node (ref "L42") (pin "2") (pinfunction "2_2") (pintype "passive"))
      (node (ref "R132") (pin "1") (pinfunction "1_1") (pintype "passive"))
    )
    (net (code "106") (name "Net-(C242-Pad2)") (class "Default")
      (node (ref "C242") (pin "2") (pinfunction "2_2") (pintype "passive"))
      (node (ref "C260") (pin "2") (pinfunction "2_2") (pintype "passive"))
      (node (ref "C264") (pin "2") (pinfunction "2_2") (pintype "passive"))
      (node (ref "C266") (pin "2") (pinfunction "2_2") (pintype "passive"))
      (node (ref "DD10") (pin "15") (pinfunction "VDD_15") (pintype "passive"))
      (node (ref "DD10") (pin "16") (pinfunction "VDD_16") (pintype "passive"))
      (node (ref "DD10") (pin "17") (pinfunction "VDD_17") (pintype "passive"))
      (node (ref "DD10") (pin "5") (pinfunction "VDD_5") (pintype "passive"))
      (node (ref "DD10") (pin "6") (pinfunction "VDD_6") (pintype "passive"))
      (node (ref "L37") (pin "2") (pinfunction "2_2") (pintype "passive"))
      (node (ref "R123") (pin "2") (pinfunction "2_2") (pintype "passive"))
    )
    (net (code "107") (name "Net-(C243-Pad1)") (class "Default")
      (node (ref "C243") (pin "1") (pinfunction "1_1") (pintype "passive"))
      (node (ref "C250") (pin "2") (pinfunction "2_2") (pintype "passive"))
      (node (ref "L43") (pin "2") (pinfunction "2_2") (pintype "passive"))
      (node (ref "R133") (pin "1") (pinfunction "1_1") (pintype "passive"))
    )
    (net (code "108") (name "Net-(C244-Pad1)") (class "Default")
      (node (ref "C244") (pin "1") (pinfunction "1_1") (pintype "passive"))
      (node (ref "C250") (pin "1") (pinfunction "1_1") (pintype "passive"))
      (node (ref "L44") (pin "2") (pinfunction "2_2") (pintype "passive"))
      (node (ref "R134") (pin "1") (pinfunction "1_1") (pintype "passive"))
    )
    (net (code "109") (name "Net-(C245-Pad2)") (class "Default")
      (node (ref "C245") (pin "2") (pinfunction "2_2") (pintype "passive"))
      (node (ref "C247") (pin "2") (pinfunction "2_2") (pintype "passive"))
      (node (ref "C252") (pin "2") (pinfunction "2_2") (pintype "passive"))
      (node (ref "C265") (pin "2") (pinfunction "2_2") (pintype "passive"))
      (node (ref "DD11") (pin "15") (pinfunction "VDD_15") (pintype "passive"))
      (node (ref "DD11") (pin "16") (pinfunction "VDD_16") (pintype "passive"))
      (node (ref "DD11") (pin "17") (pinfunction "VDD_17") (pintype "passive"))
      (node (ref "DD11") (pin "5") (pinfunction "VDD_5") (pintype "passive"))
      (node (ref "DD11") (pin "6") (pinfunction "VDD_6") (pintype "passive"))
      (node (ref "L38") (pin "2") (pinfunction "2_2") (pintype "passive"))
      (node (ref "R125") (pin "2") (pinfunction "2_2") (pintype "passive"))
    )
    (net (code "110") (name "Net-(C256-Pad2)") (class "Default")
      (node (ref "C256") (pin "2") (pinfunction "2_2") (pintype "passive"))
      (node (ref "C262") (pin "2") (pinfunction "2_2") (pintype "passive"))
      (node (ref "C267") (pin "2") (pinfunction "2_2") (pintype "passive"))
      (node (ref "DD10") (pin "32") (pinfunction "OVDD_32") (pintype "passive"))
      (node (ref "DD10") (pin "49") (pinfunction "OVDD_49") (pintype "passive"))
      (node (ref "L39") (pin "2") (pinfunction "2_2") (pintype "passive"))
      (node (ref "R117") (pin "1") (pinfunction "1_1") (pintype "passive"))
      (node (ref "R119") (pin "1") (pinfunction "1_1") (pintype "passive"))
      (node (ref "R124") (pin "1") (pinfunction "1_1") (pintype "passive"))
    )
    (net (code "111") (name "Net-(C259-Pad2)") (class "Default")
      (node (ref "C259") (pin "2") (pinfunction "2_2") (pintype "passive"))
      (node (ref "C263") (pin "2") (pinfunction "2_2") (pintype "passive"))
      (node (ref "C269") (pin "2") (pinfunction "2_2") (pintype "passive"))
      (node (ref "DD11") (pin "32") (pinfunction "OVDD_32") (pintype "passive"))
      (node (ref "DD11") (pin "49") (pinfunction "OVDD_49") (pintype "passive"))
      (node (ref "L40") (pin "2") (pinfunction "2_2") (pintype "passive"))
      (node (ref "R118") (pin "1") (pinfunction "1_1") (pintype "passive"))
      (node (ref "R121") (pin "1") (pinfunction "1_1") (pintype "passive"))
      (node (ref "R127") (pin "1") (pinfunction "1_1") (pintype "passive"))
    )
    (net (code "112") (name "Net-(DA13-EN)") (class "Default")
      (node (ref "C182") (pin "2") (pinfunction "2_2") (pintype "passive"))
      (node (ref "C184") (pin "2") (pinfunction "2_2") (pintype "passive"))
      (node (ref "C185") (pin "2") (pinfunction "2_2") (pintype "passive"))
      (node (ref "DA13") (pin "13") (pinfunction "EN_13") (pintype "passive"))
      (node (ref "DA13") (pin "15") (pinfunction "IN_15") (pintype "passive"))
      (node (ref "DA13") (pin "16") (pinfunction "IN_16") (pintype "passive"))
      (node (ref "L22") (pin "2") (pinfunction "2_2") (pintype "passive"))
    )
    (net (code "113") (name "Net-(DA13-NR)") (class "Default")
      (node (ref "C191") (pin "2") (pinfunction "2_2") (pintype "passive"))
      (node (ref "DA13") (pin "14") (pinfunction "NR_14") (pintype "passive"))
    )
    (net (code "114") (name "Net-(DA13-SENSE)") (class "Default")
      (node (ref "C192") (pin "2") (pinfunction "2_2") (pintype "passive"))
      (node (ref "DA13") (pin "1") (pinfunction "OUT_1") (pintype "passive"))
      (node (ref "DA13") (pin "20") (pinfunction "OUT_20") (pintype "passive"))
      (node (ref "DA13") (pin "3") (pinfunction "SENSE_3") (pintype "passive"))
      (node (ref "L23") (pin "2") (pinfunction "2_2") (pintype "passive"))
      (node (ref "L24") (pin "2") (pinfunction "2_2") (pintype "passive"))
      (node (ref "L25") (pin "2") (pinfunction "2_2") (pintype "passive"))
      (node (ref "L30") (pin "1") (pinfunction "1_1") (pintype "passive"))
    )
    (net (code "115") (name "Net-(DA14-C16)") (class "Default")
      (node (ref "DA14") (pin "1") (pinfunction "C16_1") (pintype "passive"))
      (node (ref "R96") (pin "2") (pinfunction "2_2") (pintype "passive"))
    )
    (net (code "116") (name "Net-(DA14-CLOCK)") (class "Default")
      (node (ref "C186") (pin "2") (pinfunction "2_2") (pintype "passive"))
      (node (ref "DA14") (pin "4") (pinfunction "CLOCK_4") (pintype "input"))
      (node (ref "R89") (pin "1") (pinfunction "1_1") (pintype "passive"))
    )
    (net (code "117") (name "Net-(DA14-DATA)") (class "Default")
      (node (ref "DA14") (pin "3") (pinfunction "DATA_3") (pintype "input"))
      (node (ref "R88") (pin "1") (pinfunction "1_1") (pintype "passive"))
    )
    (net (code "118") (name "Net-(DA14-LE)") (class "Default")
      (node (ref "C188") (pin "2") (pinfunction "2_2") (pintype "passive"))
      (node (ref "DA14") (pin "5") (pinfunction "LE_5") (pintype "input"))
      (node (ref "R90") (pin "1") (pinfunction "1_1") (pintype "passive"))
      (node (ref "R94") (pin "1") (pinfunction "1_1") (pintype "passive"))
    )
    (net (code "119") (name "Net-(DA14-PUP1)") (class "Default")
      (node (ref "C198") (pin "2") (pinfunction "2_2") (pintype "passive"))
      (node (ref "C202") (pin "2") (pinfunction "2_2") (pintype "passive"))
      (node (ref "DA14") (pin "13") (pinfunction "P/S_13") (pintype "passive"))
      (node (ref "DA14") (pin "6") (pinfunction "Vdd_6") (pintype "power_in"))
      (node (ref "DA14") (pin "7") (pinfunction "PUP1_7") (pintype "passive"))
      (node (ref "DA14") (pin "8") (pinfunction "PUP2_8") (pintype "passive"))
      (node (ref "DA14") (pin "9") (pinfunction "Vdd_9") (pintype "power_in"))
      (node (ref "L27") (pin "1") (pinfunction "1_1") (pintype "passive"))
    )
    (net (code "120") (name "Net-(DA14-RFIN)") (class "Default")
      (node (ref "DA14") (pin "2") (pinfunction "RFIN_2") (pintype "passive"))
      (node (ref "XW1") (pin "1") (pinfunction "1_1") (pintype "passive"))
    )
    (net (code "121") (name "Net-(DA14-RFOUT)") (class "Default")
      (node (ref "C204") (pin "2") (pinfunction "2_2") (pintype "passive"))
      (node (ref "C206") (pin "2") (pinfunction "2_2") (pintype "passive"))
      (node (ref "DA14") (pin "14") (pinfunction "RFOUT_14") (pintype "passive"))
      (node (ref "L26") (pin "1") (pinfunction "1_1") (pintype "passive"))
    )
    (net (code "122") (name "Net-(DA15-C16)") (class "Default")
      (node (ref "DA15") (pin "1") (pinfunction "C16_1") (pintype "passive"))
      (node (ref "R97") (pin "2") (pinfunction "2_2") (pintype "passive"))
    )
    (net (code "123") (name "Net-(DA15-CLOCK)") (class "Default")
      (node (ref "C187") (pin "2") (pinfunction "2_2") (pintype "passive"))
      (node (ref "DA15") (pin "4") (pinfunction "CLOCK_4") (pintype "input"))
      (node (ref "R92") (pin "1") (pinfunction "1_1") (pintype "passive"))
    )
    (net (code "124") (name "Net-(DA15-DATA)") (class "Default")
      (node (ref "DA15") (pin "3") (pinfunction "DATA_3") (pintype "input"))
      (node (ref "R91") (pin "1") (pinfunction "1_1") (pintype "passive"))
    )
    (net (code "125") (name "Net-(DA15-LE)") (class "Default")
      (node (ref "C189") (pin "2") (pinfunction "2_2") (pintype "passive"))
      (node (ref "DA15") (pin "5") (pinfunction "LE_5") (pintype "input"))
      (node (ref "R93") (pin "1") (pinfunction "1_1") (pintype "passive"))
      (node (ref "R95") (pin "1") (pinfunction "1_1") (pintype "passive"))
    )
    (net (code "126") (name "Net-(DA15-PUP1)") (class "Default")
      (node (ref "C199") (pin "2") (pinfunction "2_2") (pintype "passive"))
      (node (ref "C203") (pin "2") (pinfunction "2_2") (pintype "passive"))
      (node (ref "DA15") (pin "13") (pinfunction "P/S_13") (pintype "passive"))
      (node (ref "DA15") (pin "6") (pinfunction "Vdd_6") (pintype "power_in"))
      (node (ref "DA15") (pin "7") (pinfunction "PUP1_7") (pintype "passive"))
      (node (ref "DA15") (pin "8") (pinfunction "PUP2_8") (pintype "passive"))
      (node (ref "DA15") (pin "9") (pinfunction "Vdd_9") (pintype "power_in"))
      (node (ref "L29") (pin "1") (pinfunction "1_1") (pintype "passive"))
    )
    (net (code "127") (name "Net-(DA15-RFIN)") (class "Default")
      (node (ref "DA15") (pin "2") (pinfunction "RFIN_2") (pintype "passive"))
      (node (ref "XW2") (pin "1") (pinfunction "1_1") (pintype "passive"))
    )
    (net (code "128") (name "Net-(DA15-RFOUT)") (class "Default")
      (node (ref "C205") (pin "2") (pinfunction "2_2") (pintype "passive"))
      (node (ref "C207") (pin "2") (pinfunction "2_2") (pintype "passive"))
      (node (ref "DA15") (pin "14") (pinfunction "RFOUT_14") (pintype "passive"))
      (node (ref "L28") (pin "1") (pinfunction "1_1") (pintype "passive"))
    )
    (net (code "129") (name "Net-(DA16-EN)") (class "Default")
      (node (ref "C217") (pin "2") (pinfunction "2_2") (pintype "passive"))
      (node (ref "C220") (pin "2") (pinfunction "2_2") (pintype "passive"))
      (node (ref "C222") (pin "2") (pinfunction "2_2") (pintype "passive"))
      (node (ref "DA16") (pin "13") (pinfunction "EN_13") (pintype "passive"))
      (node (ref "DA16") (pin "15") (pinfunction "IN_15") (pintype "passive"))
      (node (ref "DA16") (pin "16") (pinfunction "IN_16") (pintype "passive"))
      (node (ref "L31") (pin "2") (pinfunction "2_2") (pintype "passive"))
    )
    (net (code "130") (name "Net-(DA16-NR)") (class "Default")
      (node (ref "C230") (pin "2") (pinfunction "2_2") (pintype "passive"))
      (node (ref "DA16") (pin "14") (pinfunction "NR_14") (pintype "passive"))
    )
    (net (code "131") (name "Net-(DA16-SENSE)") (class "Default")
      (node (ref "C234") (pin "2") (pinfunction "2_2") (pintype "passive"))
      (node (ref "DA16") (pin "1") (pinfunction "OUT_1") (pintype "passive"))
      (node (ref "DA16") (pin "20") (pinfunction "OUT_20") (pintype "passive"))
      (node (ref "DA16") (pin "3") (pinfunction "SENSE_3") (pintype "passive"))
      (node (ref "L27") (pin "2") (pinfunction "2_2") (pintype "passive"))
      (node (ref "L35") (pin "1") (pinfunction "1_1") (pintype "passive"))
      (node (ref "L37") (pin "1") (pinfunction "1_1") (pintype "passive"))
      (node (ref "L39") (pin "1") (pinfunction "1_1") (pintype "passive"))
    )
    (net (code "132") (name "Net-(DA17-EN)") (class "Default")
      (node (ref "C219") (pin "2") (pinfunction "2_2") (pintype "passive"))
      (node (ref "C221") (pin "2") (pinfunction "2_2") (pintype "passive"))
      (node (ref "C223") (pin "2") (pinfunction "2_2") (pintype "passive"))
      (node (ref "DA17") (pin "13") (pinfunction "EN_13") (pintype "passive"))
      (node (ref "DA17") (pin "15") (pinfunction "IN_15") (pintype "passive"))
      (node (ref "DA17") (pin "16") (pinfunction "IN_16") (pintype "passive"))
      (node (ref "L32") (pin "2") (pinfunction "2_2") (pintype "passive"))
    )
    (net (code "133") (name "Net-(DA17-NR)") (class "Default")
      (node (ref "C231") (pin "2") (pinfunction "2_2") (pintype "passive"))
      (node (ref "DA17") (pin "14") (pinfunction "NR_14") (pintype "passive"))
    )
    (net (code "134") (name "Net-(DA17-SENSE)") (class "Default")
      (node (ref "C235") (pin "2") (pinfunction "2_2") (pintype "passive"))
      (node (ref "DA17") (pin "1") (pinfunction "OUT_1") (pintype "passive"))
      (node (ref "DA17") (pin "20") (pinfunction "OUT_20") (pintype "passive"))
      (node (ref "DA17") (pin "3") (pinfunction "SENSE_3") (pintype "passive"))
      (node (ref "L29") (pin "2") (pinfunction "2_2") (pintype "passive"))
      (node (ref "L36") (pin "1") (pinfunction "1_1") (pintype "passive"))
      (node (ref "L38") (pin "1") (pinfunction "1_1") (pintype "passive"))
      (node (ref "L40") (pin "1") (pinfunction "1_1") (pintype "passive"))
    )
    (net (code "135") (name "Net-(DA18-OUT+)") (class "Default")
      (node (ref "DA18") (pin "8") (pinfunction "OUT+_8") (pintype "passive"))
      (node (ref "R109") (pin "1") (pinfunction "1_1") (pintype "passive"))
    )
    (net (code "136") (name "Net-(DA18-OUT-)") (class "Default")
      (node (ref "DA18") (pin "5") (pinfunction "OUT-_5") (pintype "passive"))
      (node (ref "R110") (pin "1") (pinfunction "1_1") (pintype "passive"))
    )
    (net (code "137") (name "Net-(DA18-VOCM)") (class "Default")
      (node (ref "C236") (pin "2") (pinfunction "2_2") (pintype "passive"))
      (node (ref "DA18") (pin "2") (pinfunction "VOCM_2") (pintype "passive"))
      (node (ref "R115") (pin "1") (pinfunction "1_1") (pintype "passive"))
    )
    (net (code "138") (name "Net-(DA19-OUT+)") (class "Default")
      (node (ref "DA19") (pin "8") (pinfunction "OUT+_8") (pintype "passive"))
      (node (ref "R111") (pin "1") (pinfunction "1_1") (pintype "passive"))
    )
    (net (code "139") (name "Net-(DA19-OUT-)") (class "Default")
      (node (ref "DA19") (pin "5") (pinfunction "OUT-_5") (pintype "passive"))
      (node (ref "R112") (pin "1") (pinfunction "1_1") (pintype "passive"))
    )
    (net (code "140") (name "Net-(DA19-VOCM)") (class "Default")
      (node (ref "C237") (pin "2") (pinfunction "2_2") (pintype "passive"))
      (node (ref "DA19") (pin "2") (pinfunction "VOCM_2") (pintype "passive"))
      (node (ref "R116") (pin "1") (pinfunction "1_1") (pintype "passive"))
    )
    (net (code "141") (name "Net-(DD8-OUT)") (class "Default")
      (node (ref "DD8") (pin "3") (pinfunction "Vsense_3") (pintype "passive"))
      (node (ref "DD8") (pin "4") (pinfunction "OUT_4") (pintype "passive"))
      (node (ref "R98") (pin "1") (pinfunction "1_1") (pintype "passive"))
    )
    (net (code "142") (name "Net-(DD8-VDD)") (class "Default")
      (node (ref "C183") (pin "1") (pinfunction "1_1") (pintype "passive"))
      (node (ref "DD8") (pin "1") (pinfunction "VDD_1") (pintype "passive"))
      (node (ref "L23") (pin "1") (pinfunction "1_1") (pintype "passive"))
      (node (ref "R99") (pin "2") (pinfunction "2_2") (pintype "passive"))
    )
    (net (code "143") (name "Net-(DD8-VREF)") (class "Default")
      (node (ref "C190") (pin "1") (pinfunction "1_1") (pintype "passive"))
      (node (ref "DD8") (pin "2") (pinfunction "VREF_2") (pintype "passive"))
      (node (ref "R99") (pin "1") (pinfunction "1_1") (pintype "passive"))
    )
    (net (code "144") (name "Net-(DD9-CLK)") (class "Default")
      (node (ref "C201") (pin "1") (pinfunction "1_1") (pintype "passive"))
      (node (ref "DD9") (pin "1") (pinfunction "CLK_1") (pintype "passive"))
    )
    (net (code "145") (name "Net-(DD9-VREF)") (class "Default")
      (node (ref "C209") (pin "1") (pinfunction "1_1") (pintype "passive"))
      (node (ref "DD9") (pin "2") (pinfunction "VT_2") (pintype "passive"))
      (node (ref "DD9") (pin "3") (pinfunction "VREF_3") (pintype "passive"))
      (node (ref "DD9") (pin "4") (pinfunction "~{CLK}_4") (pintype "passive"))
    )
    (net (code "146") (name "Net-(DD10-AIN+)") (class "Default")
      (node (ref "DD10") (pin "8") (pinfunction "AIN+_8") (pintype "passive"))
      (node (ref "R131") (pin "2") (pinfunction "2_2") (pintype "passive"))
    )
    (net (code "147") (name "Net-(DD10-AIN-)") (class "Default")
      (node (ref "DD10") (pin "9") (pinfunction "AIN-_9") (pintype "passive"))
      (node (ref "R132") (pin "2") (pinfunction "2_2") (pintype "passive"))
    )
    (net (code "148") (name "Net-(DD10-OF+{slash}OFA)") (class "Default")
      (node (ref "DD10") (pin "60") (pinfunction "OF+/OFA_60") (pintype "passive"))
      (node (ref "R135") (pin "2") (pinfunction "2_2") (pintype "passive"))
    )
    (net (code "149") (name "Net-(DD10-OF-{slash}DA15)") (class "Default")
      (node (ref "DD10") (pin "59") (pinfunction "OF-/DA15_59") (pintype "passive"))
      (node (ref "R135") (pin "1") (pinfunction "1_1") (pintype "passive"))
    )
    (net (code "150") (name "Net-(DD10-SENSE)") (class "Default")
      (node (ref "C255") (pin "2") (pinfunction "2_2") (pintype "passive"))
      (node (ref "DD10") (pin "1") (pinfunction "SENSE_1") (pintype "passive"))
      (node (ref "R123") (pin "1") (pinfunction "1_1") (pintype "passive"))
    )
    (net (code "151") (name "Net-(DD10-VCM)") (class "Default")
      (node (ref "C254") (pin "2") (pinfunction "2_2") (pintype "passive"))
      (node (ref "DD10") (pin "3") (pinfunction "VCM_3") (pintype "passive"))
      (node (ref "R115") (pin "2") (pinfunction "2_2") (pintype "passive"))
    )
    (net (code "152") (name "Net-(DD11-AIN+)") (class "Default")
      (node (ref "DD11") (pin "8") (pinfunction "AIN+_8") (pintype "passive"))
      (node (ref "R133") (pin "2") (pinfunction "2_2") (pintype "passive"))
    )
    (net (code "153") (name "Net-(DD11-AIN-)") (class "Default")
      (node (ref "DD11") (pin "9") (pinfunction "AIN-_9") (pintype "passive"))
      (node (ref "R134") (pin "2") (pinfunction "2_2") (pintype "passive"))
    )
    (net (code "154") (name "Net-(DD11-OF+{slash}OFA)") (class "Default")
      (node (ref "DD11") (pin "60") (pinfunction "OF+/OFA_60") (pintype "passive"))
      (node (ref "R136") (pin "2") (pinfunction "2_2") (pintype "passive"))
    )
    (net (code "155") (name "Net-(DD11-OF-{slash}DA15)") (class "Default")
      (node (ref "DD11") (pin "59") (pinfunction "OF-/DA15_59") (pintype "passive"))
      (node (ref "R136") (pin "1") (pinfunction "1_1") (pintype "passive"))
    )
    (net (code "156") (name "Net-(DD11-SENSE)") (class "Default")
      (node (ref "C258") (pin "2") (pinfunction "2_2") (pintype "passive"))
      (node (ref "DD11") (pin "1") (pinfunction "SENSE_1") (pintype "passive"))
      (node (ref "R125") (pin "1") (pinfunction "1_1") (pintype "passive"))
    )
    (net (code "157") (name "Net-(DD11-VCM)") (class "Default")
      (node (ref "C257") (pin "2") (pinfunction "2_2") (pintype "passive"))
      (node (ref "DD11") (pin "3") (pinfunction "VCM_3") (pintype "passive"))
      (node (ref "R116") (pin "2") (pinfunction "2_2") (pintype "passive"))
    )
    (net (code "158") (name "Net-(G2-CTRL)") (class "Default")
      (node (ref "C195") (pin "1") (pinfunction "1_1") (pintype "passive"))
      (node (ref "C197") (pin "2") (pinfunction "2_2") (pintype "passive"))
      (node (ref "G2") (pin "1") (pinfunction "CTRL_1") (pintype "passive"))
      (node (ref "R100") (pin "2") (pinfunction "2_2") (pintype "passive"))
    )
    (net (code "159") (name "Net-(G2-OUT)") (class "Default")
      (node (ref "C201") (pin "2") (pinfunction "2_2") (pintype "passive"))
      (node (ref "G2") (pin "3") (pinfunction "OUT_3") (pintype "passive"))
    )
    (net (code "160") (name "Net-(G2-VDD)") (class "Default")
      (node (ref "C194") (pin "2") (pinfunction "2_2") (pintype "passive"))
      (node (ref "C196") (pin "2") (pinfunction "2_2") (pintype "passive"))
      (node (ref "G2") (pin "4") (pinfunction "VDD_4") (pintype "passive"))
      (node (ref "L24") (pin "1") (pinfunction "1_1") (pintype "passive"))
    )
    (net (code "161") (name "Net-(T1-PRIMARY_DOT)") (class "Default")
      (node (ref "C213") (pin "1") (pinfunction "1_1") (pintype "passive"))
      (node (ref "C216") (pin "2") (pinfunction "2_2") (pintype "passive"))
      (node (ref "L33") (pin "2") (pinfunction "2_2") (pintype "passive"))
      (node (ref "T1") (pin "5") (pinfunction "PRIMARY_DOT_5") (pintype "passive"))
    )
    (net (code "162") (name "Net-(T1-SECONDARY)") (class "Default")
      (node (ref "DA18") (pin "15") (pinfunction "IN-_15") (pintype "passive"))
      (node (ref "DA18") (pin "16") (pinfunction "IN-_16") (pintype "passive"))
      (node (ref "T1") (pin "3") (pinfunction "SECONDARY_3") (pintype "passive"))
    )
    (net (code "163") (name "Net-(T1-SECONDARY_DOT)") (class "Default")
      (node (ref "DA18") (pin "13") (pinfunction "IN+_13") (pintype "passive"))
      (node (ref "DA18") (pin "14") (pinfunction "IN+_14") (pintype "passive"))
      (node (ref "T1") (pin "1") (pinfunction "SECONDARY_DOT_1") (pintype "passive"))
    )
    (net (code "164") (name "Net-(T2-PRIMARY_DOT)") (class "Default")
      (node (ref "C214") (pin "1") (pinfunction "1_1") (pintype "passive"))
      (node (ref "C218") (pin "2") (pinfunction "2_2") (pintype "passive"))
      (node (ref "L34") (pin "2") (pinfunction "2_2") (pintype "passive"))
      (node (ref "T2") (pin "5") (pinfunction "PRIMARY_DOT_5") (pintype "passive"))
    )
    (net (code "165") (name "Net-(T2-SECONDARY)") (class "Default")
      (node (ref "DA19") (pin "15") (pinfunction "IN-_15") (pintype "passive"))
      (node (ref "DA19") (pin "16") (pinfunction "IN-_16") (pintype "passive"))
      (node (ref "T2") (pin "3") (pinfunction "SECONDARY_3") (pintype "passive"))
    )
    (net (code "166") (name "Net-(T2-SECONDARY_DOT)") (class "Default")
      (node (ref "DA19") (pin "13") (pinfunction "IN+_13") (pintype "passive"))
      (node (ref "DA19") (pin "14") (pinfunction "IN+_14") (pintype "passive"))
      (node (ref "T2") (pin "1") (pinfunction "SECONDARY_DOT_1") (pintype "passive"))
    )
    (net (code "167") (name "unconnected-(DA13-0P4V-Pad10)") (class "Default")
      (node (ref "DA13") (pin "10") (pinfunction "0P4V_10") (pintype "passive"))
    )
    (net (code "168") (name "unconnected-(DA13-0P8V-Pad9)") (class "Default")
      (node (ref "DA13") (pin "9") (pinfunction "0P8V_9") (pintype "passive"))
    )
    (net (code "169") (name "unconnected-(DA13-3P2V-Pad6)") (class "Default")
      (node (ref "DA13") (pin "6") (pinfunction "3P2V_6") (pintype "passive"))
    )
    (net (code "170") (name "unconnected-(DA13-6P4V1-Pad5)") (class "Default")
      (node (ref "DA13") (pin "5") (pinfunction "6P4V1_5") (pintype "passive"))
    )
    (net (code "171") (name "unconnected-(DA13-6P4V2-Pad4)") (class "Default")
      (node (ref "DA13") (pin "4") (pinfunction "6P4V2_4") (pintype "passive"))
    )
    (net (code "172") (name "unconnected-(DA16-0P4V-Pad10)") (class "Default")
      (node (ref "DA16") (pin "10") (pinfunction "0P4V_10") (pintype "passive"))
    )
    (net (code "173") (name "unconnected-(DA16-0P8V-Pad9)") (class "Default")
      (node (ref "DA16") (pin "9") (pinfunction "0P8V_9") (pintype "passive"))
    )
    (net (code "174") (name "unconnected-(DA16-3P2V-Pad6)") (class "Default")
      (node (ref "DA16") (pin "6") (pinfunction "3P2V_6") (pintype "passive"))
    )
    (net (code "175") (name "unconnected-(DA16-6P4V1-Pad5)") (class "Default")
      (node (ref "DA16") (pin "5") (pinfunction "6P4V1_5") (pintype "passive"))
    )
    (net (code "176") (name "unconnected-(DA16-6P4V2-Pad4)") (class "Default")
      (node (ref "DA16") (pin "4") (pinfunction "6P4V2_4") (pintype "passive"))
    )
    (net (code "177") (name "unconnected-(DA17-0P4V-Pad10)") (class "Default")
      (node (ref "DA17") (pin "10") (pinfunction "0P4V_10") (pintype "passive"))
    )
    (net (code "178") (name "unconnected-(DA17-0P8V-Pad9)") (class "Default")
      (node (ref "DA17") (pin "9") (pinfunction "0P8V_9") (pintype "passive"))
    )
    (net (code "179") (name "unconnected-(DA17-3P2V-Pad6)") (class "Default")
      (node (ref "DA17") (pin "6") (pinfunction "3P2V_6") (pintype "passive"))
    )
    (net (code "180") (name "unconnected-(DA17-6P4V1-Pad5)") (class "Default")
      (node (ref "DA17") (pin "5") (pinfunction "6P4V1_5") (pintype "passive"))
    )
    (net (code "181") (name "unconnected-(DA17-6P4V2-Pad4)") (class "Default")
      (node (ref "DA17") (pin "4") (pinfunction "6P4V2_4") (pintype "passive"))
    )
    (net (code "182") (name "unconnected-(DA18-OUTF+-Pad7)") (class "Default")
      (node (ref "DA18") (pin "7") (pinfunction "OUTF+_7") (pintype "passive"))
    )
    (net (code "183") (name "unconnected-(DA18-OUTF--Pad6)") (class "Default")
      (node (ref "DA18") (pin "6") (pinfunction "OUTF-_6") (pintype "passive"))
    )
    (net (code "184") (name "unconnected-(DA19-OUTF+-Pad7)") (class "Default")
      (node (ref "DA19") (pin "7") (pinfunction "OUTF+_7") (pintype "passive"))
    )
    (net (code "185") (name "unconnected-(DA19-OUTF--Pad6)") (class "Default")
      (node (ref "DA19") (pin "6") (pinfunction "OUTF-_6") (pintype "passive"))
    )
    (net (code "186") (name "unconnected-(DD9-OUT3_N-Pad6)") (class "Default")
      (node (ref "DD9") (pin "6") (pinfunction "OUT3_N_6") (pintype "passive"))
    )
    (net (code "187") (name "unconnected-(DD9-OUT3_P-Pad7)") (class "Default")
      (node (ref "DD9") (pin "7") (pinfunction "OUT3_P_7") (pintype "passive"))
    )
    (net (code "188") (name "unconnected-(T1-SECONARY_CT-Pad2)") (class "Default")
      (node (ref "T1") (pin "2") (pinfunction "SECONARY_CT_2") (pintype "passive"))
    )
    (net (code "189") (name "unconnected-(T2-SECONARY_CT-Pad2)") (class "Default")
      (node (ref "T2") (pin "2") (pinfunction "SECONARY_CT_2") (pintype "passive"))
    )
  )
)
